# blinds_v60.net
KiCad netlist of a schematic drawn in EAGLE
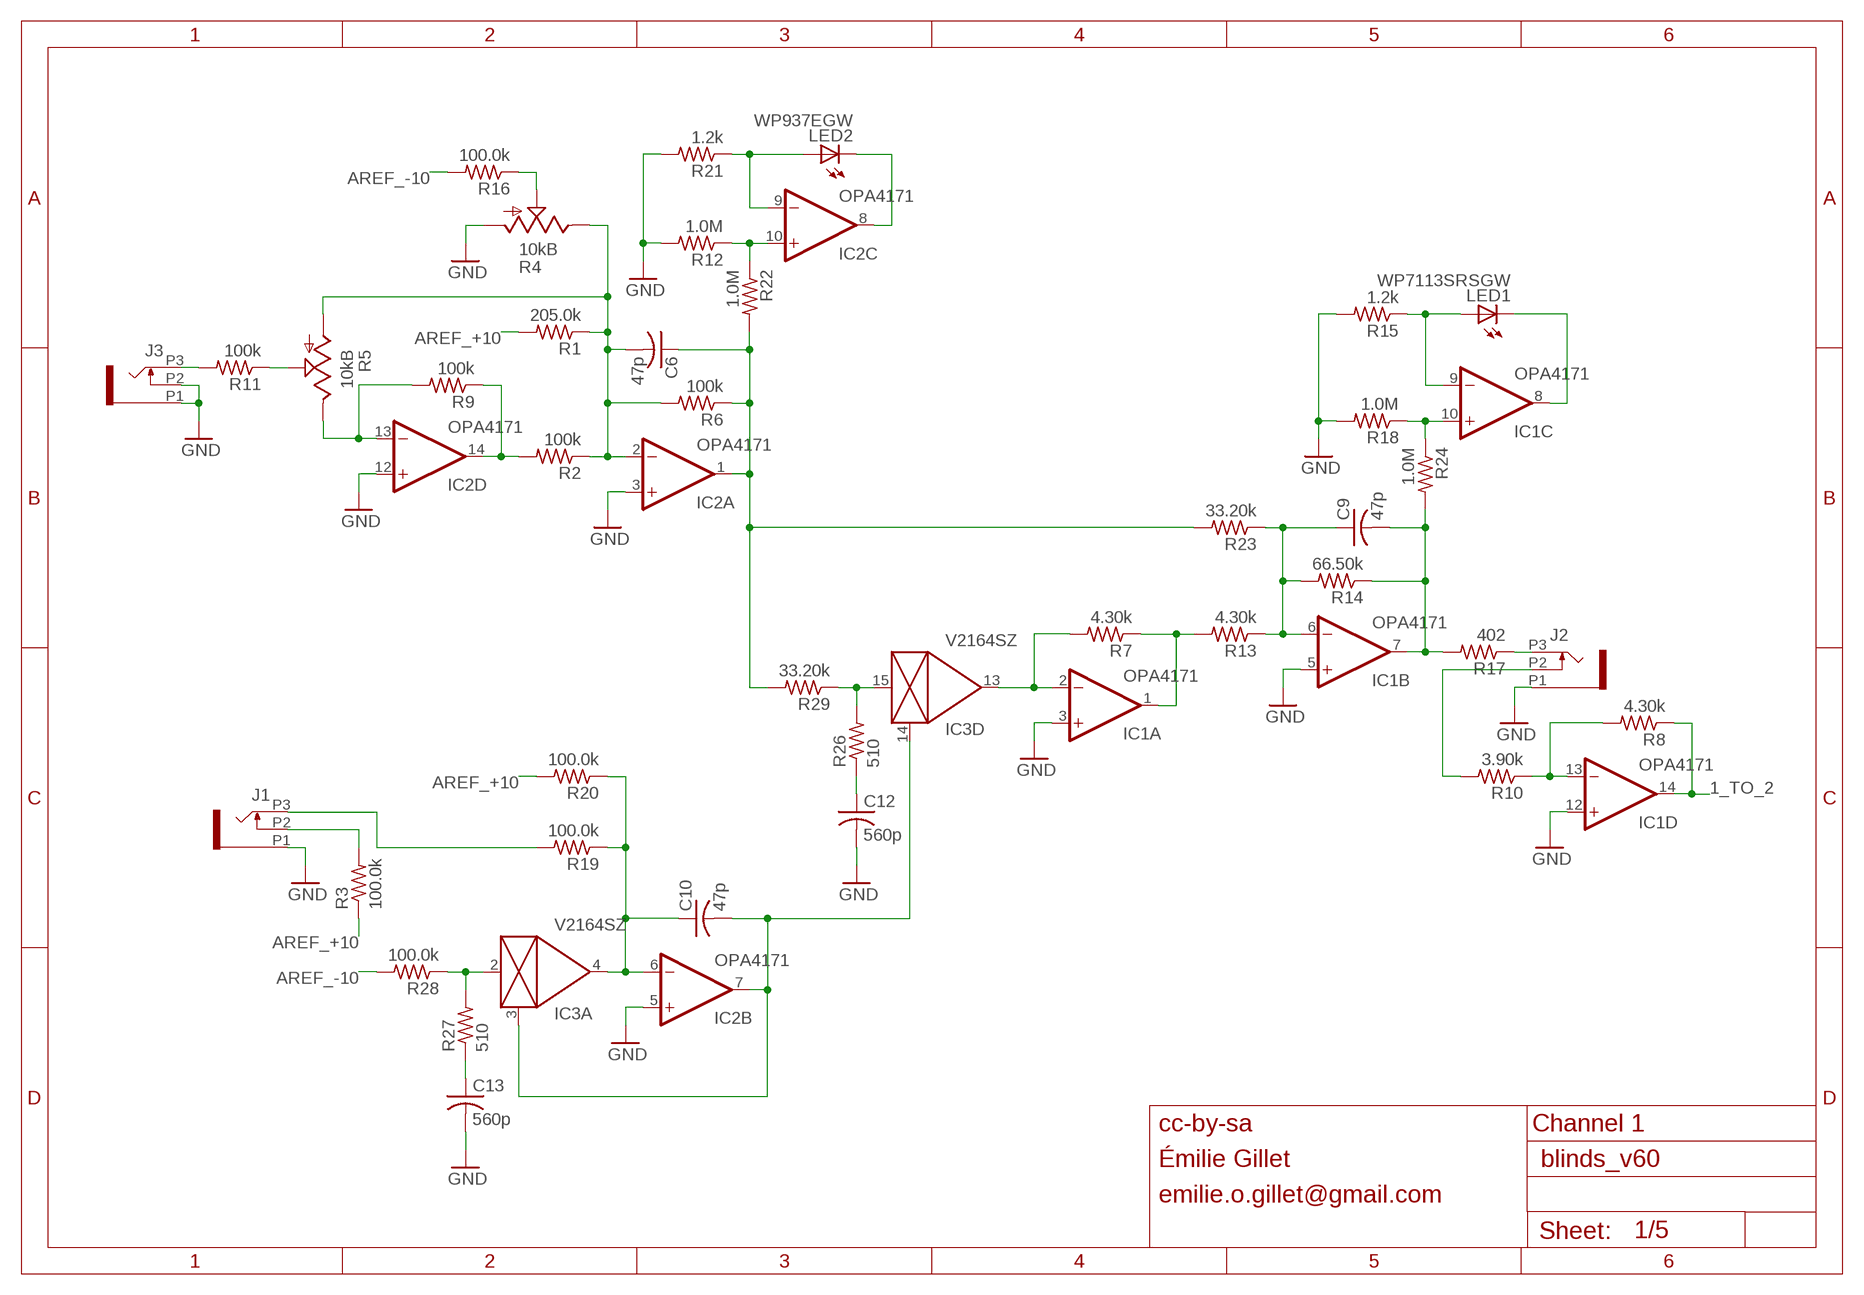
[diagram p0: schematic, sheet 1]
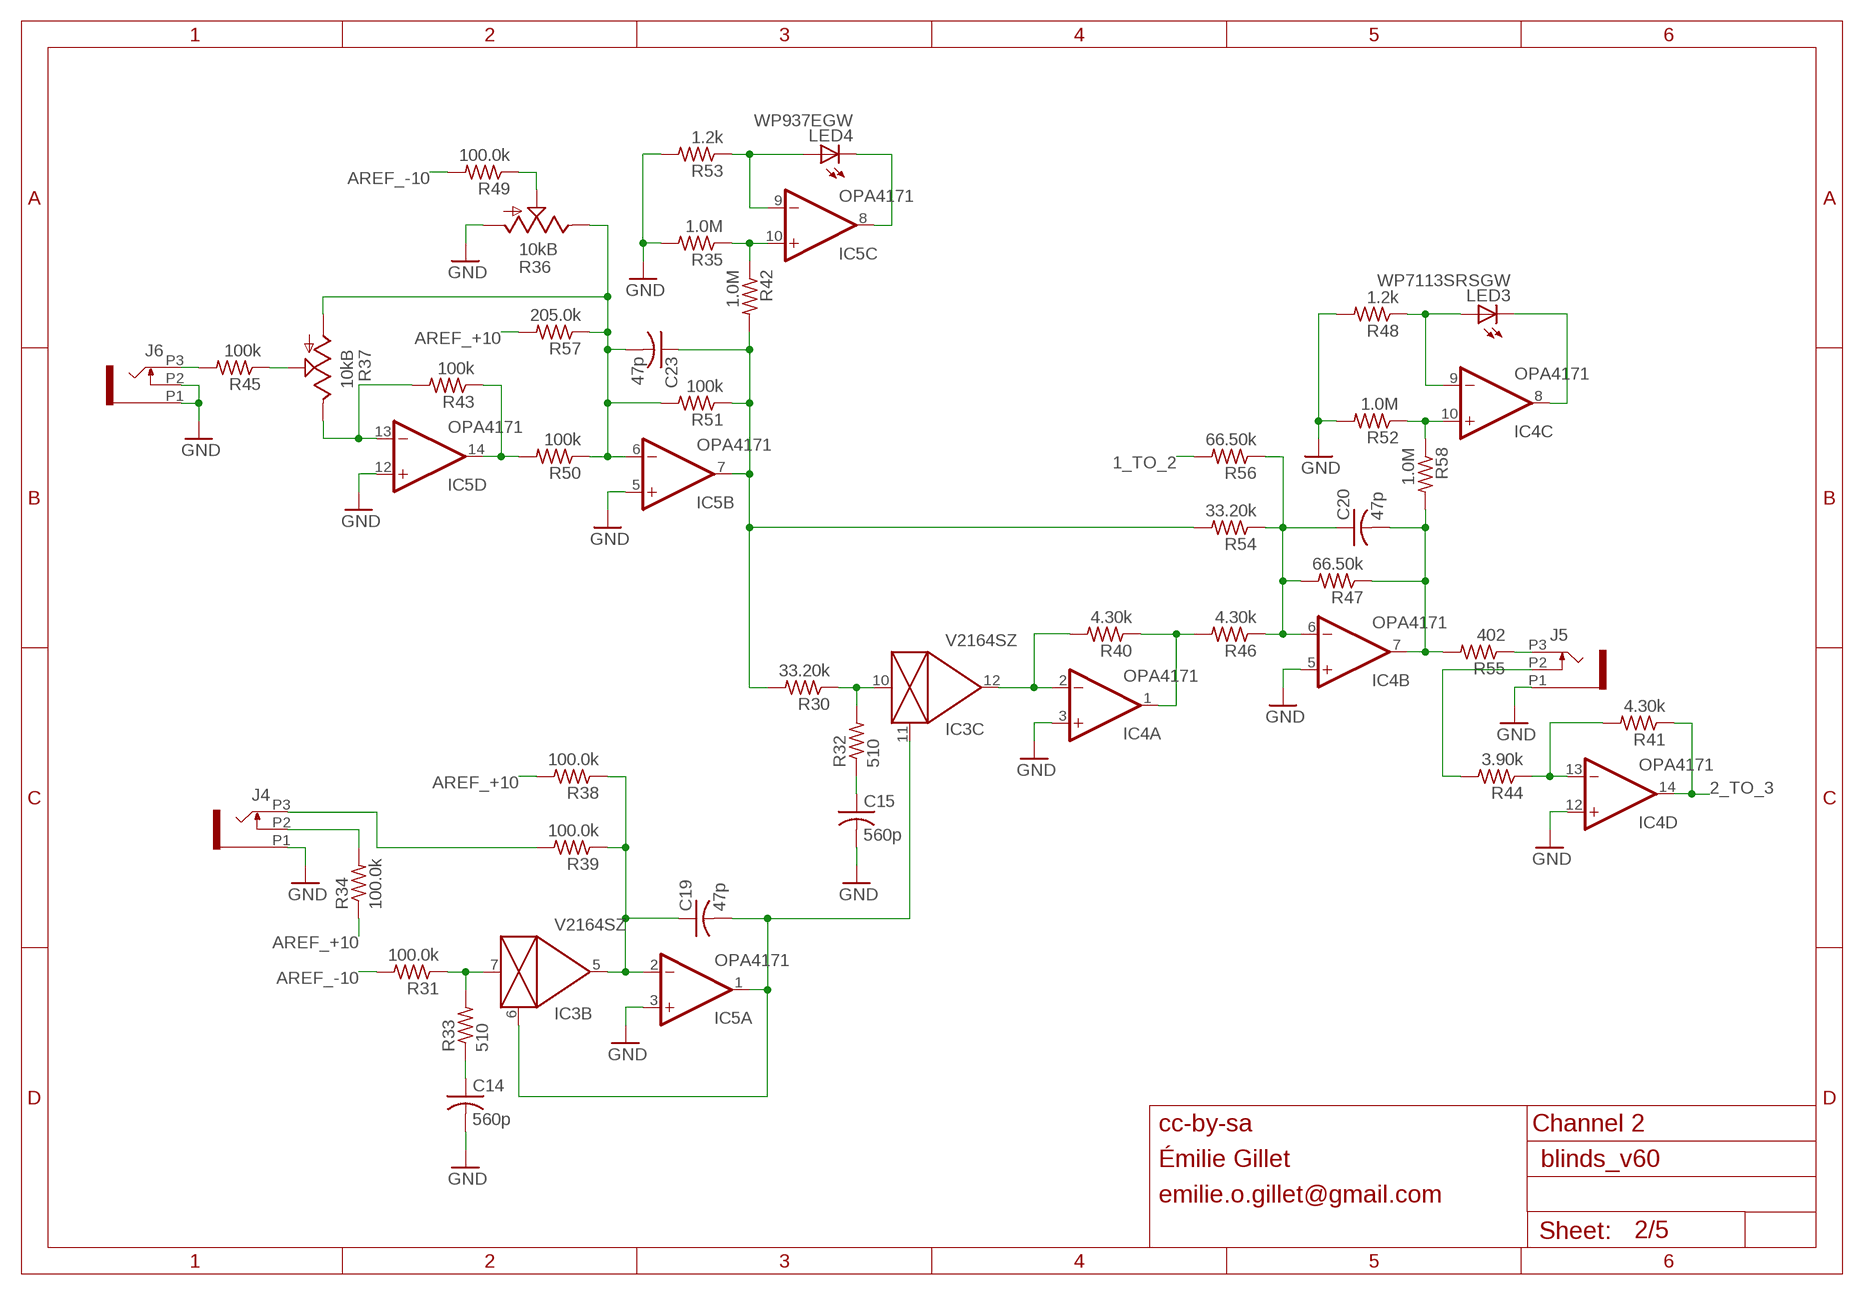
[diagram p1: schematic, sheet 2]
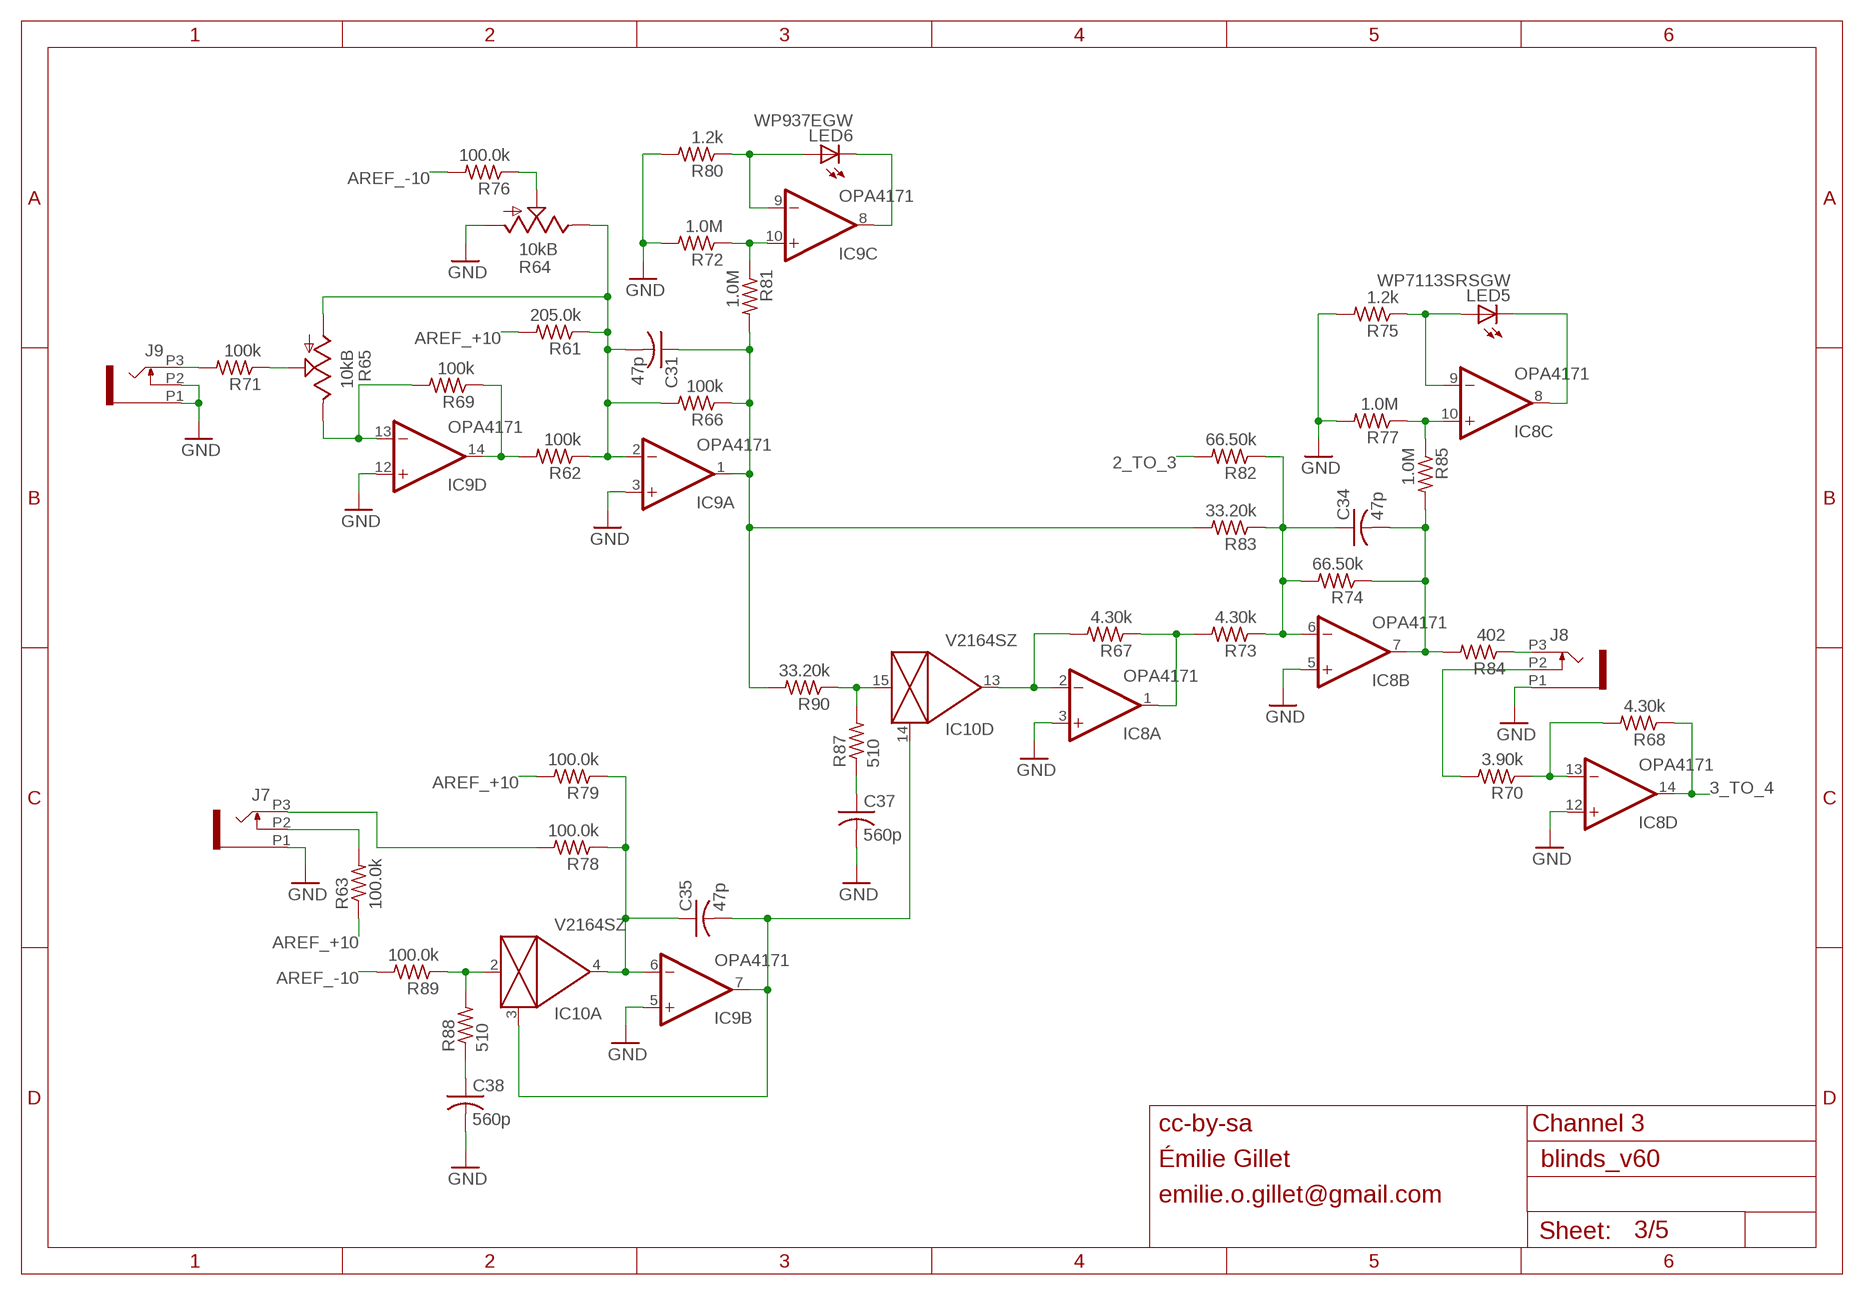
[diagram p2: schematic, sheet 3]
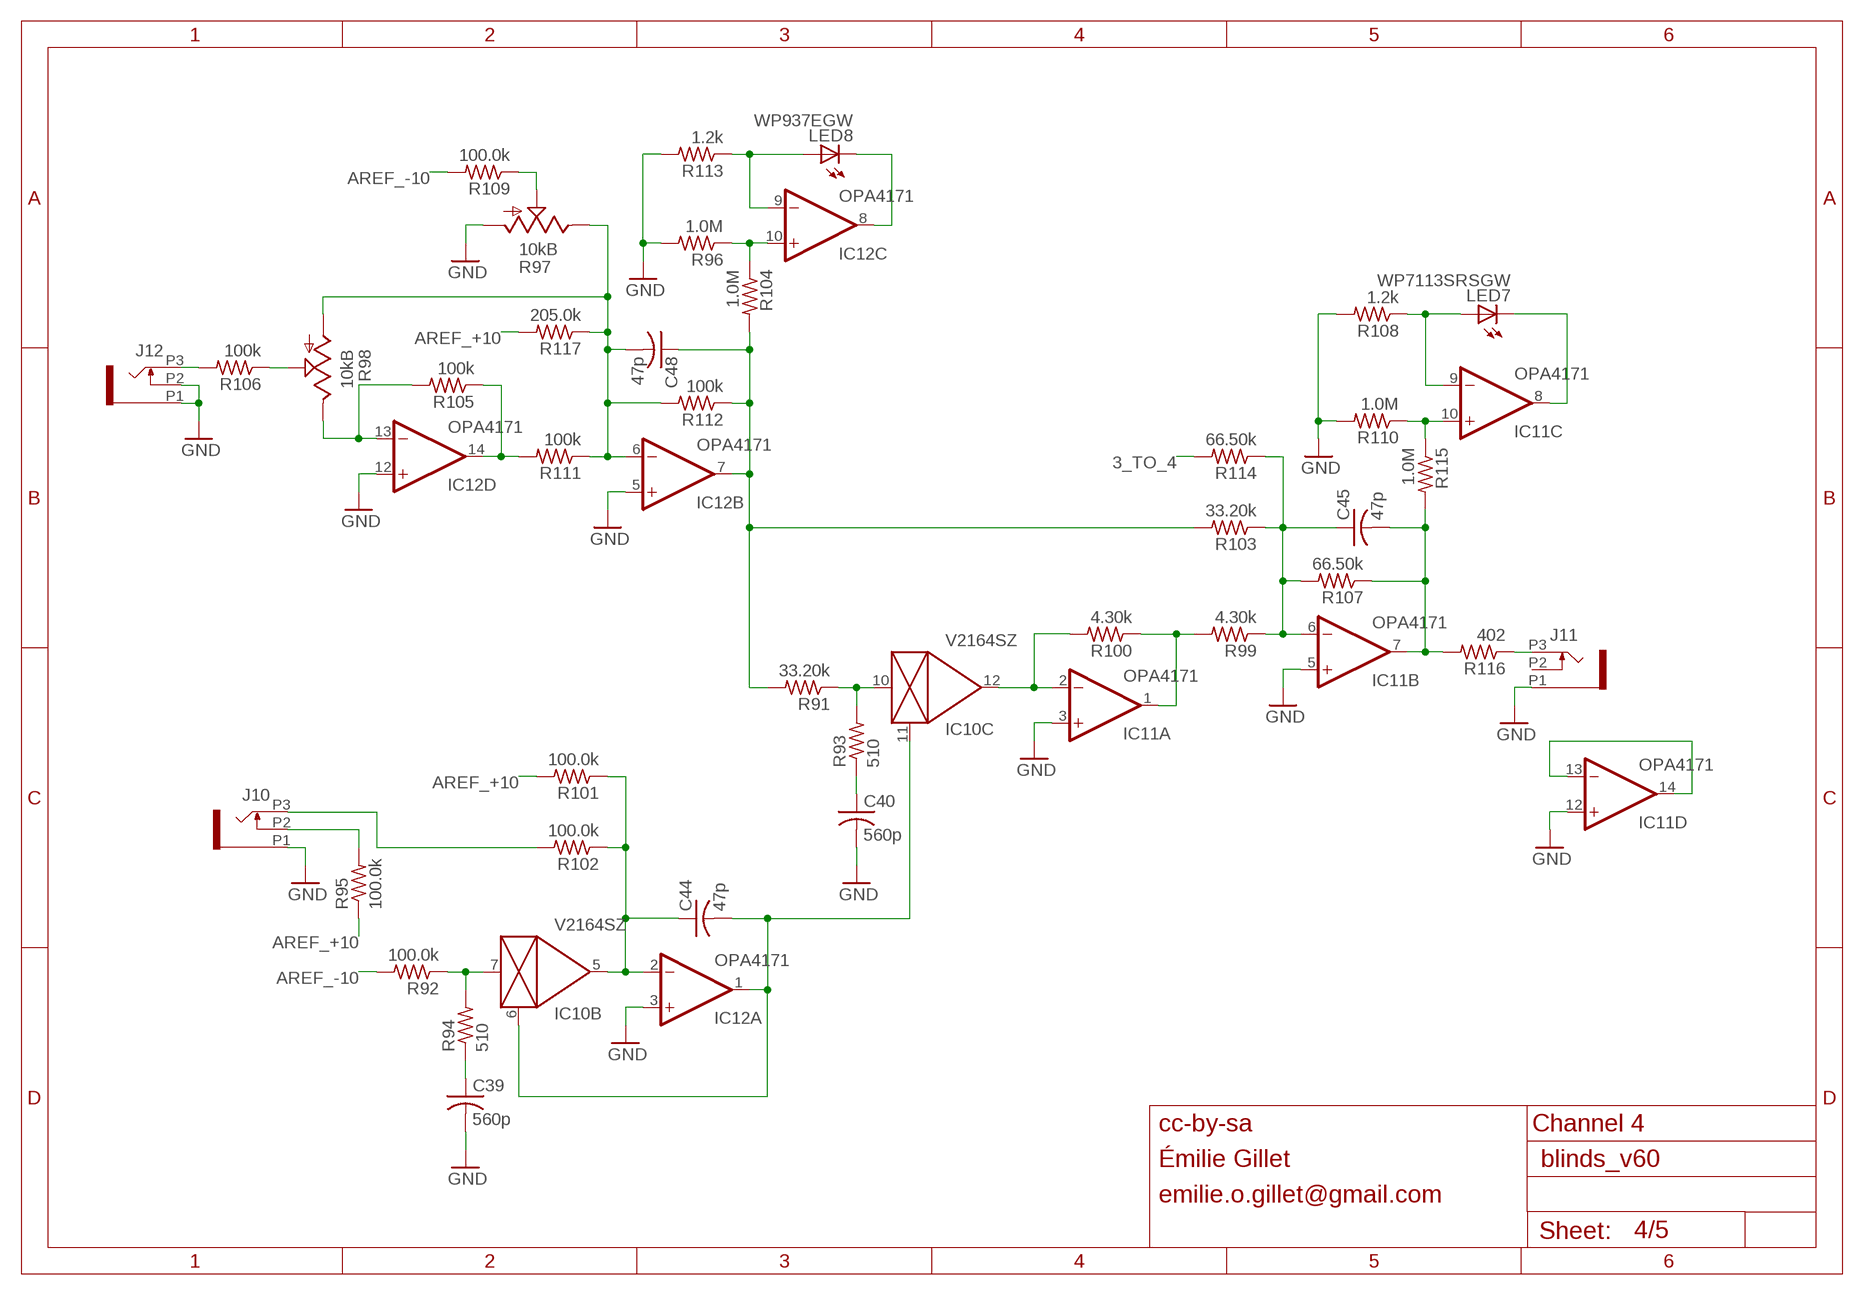
[diagram p3: schematic, sheet 4]
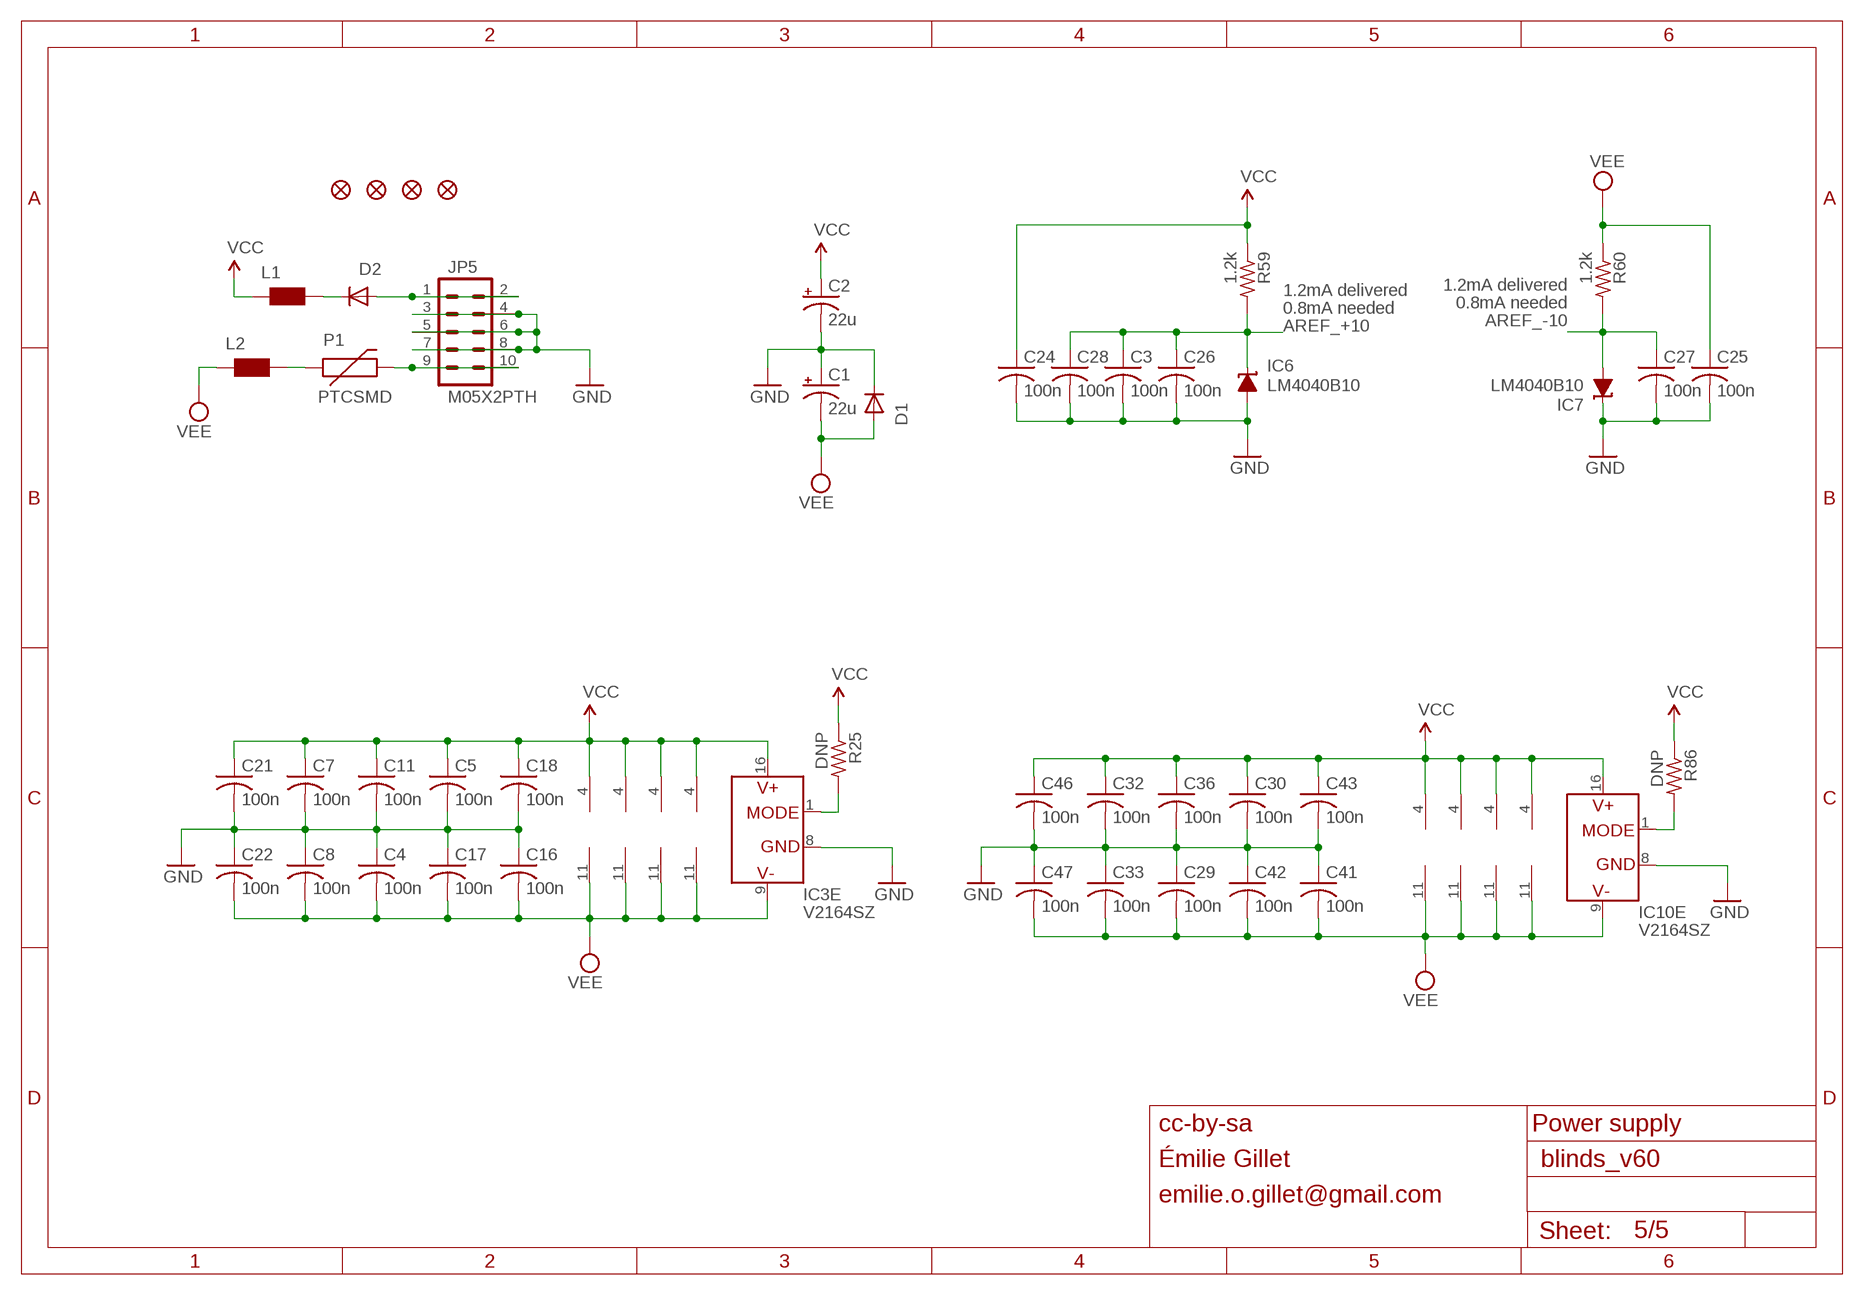
[diagram p4: schematic, sheet 5]

(export (version "E")
  (design (tool "Eeschema 10.0.6"))
  (components
    (comp (ref "C14")
      (value "560p")
      (footprint "eagle-import:C0603")
      (libsource (lib "eagle-import") (part "C-USC0603"))
    )
    (comp (ref "C15")
      (value "560p")
      (footprint "eagle-import:C0603")
      (libsource (lib "eagle-import") (part "C-USC0603"))
    )
    (comp (ref "C19")
      (value "47p")
      (footprint "eagle-import:C0603")
      (libsource (lib "eagle-import") (part "C-USC0603"))
    )
    (comp (ref "C20")
      (value "47p")
      (footprint "eagle-import:C0603")
      (libsource (lib "eagle-import") (part "C-USC0603"))
    )
    (comp (ref "C23")
      (value "47p")
      (footprint "eagle-import:C0603")
      (libsource (lib "eagle-import") (part "C-USC0603"))
    )
    (comp (ref "IC3")
      (value "V2164SZ")
      (footprint "eagle-import:SOIC16N")
      (libsource (lib "eagle-import") (part "SSM2164S"))
    )
    (comp (ref "IC4")
      (value "OPA4171")
      (footprint "eagle-import:TSSOP14")
      (libsource (lib "eagle-import") (part "TL074PW"))
    )
    (comp (ref "IC5")
      (value "OPA4171")
      (footprint "eagle-import:TSSOP14")
      (libsource (lib "eagle-import") (part "TL074PW"))
    )
    (comp (ref "J4")
      (value "PJ301_THONKICONN6")
      (footprint "eagle-import:WQP_PJ_301M6")
      (libsource (lib "eagle-import") (part "PJ301_THONKICONN6"))
    )
    (comp (ref "J5")
      (value "PJ301_THONKICONN6")
      (footprint "eagle-import:WQP_PJ_301M6")
      (libsource (lib "eagle-import") (part "PJ301_THONKICONN6"))
    )
    (comp (ref "J6")
      (value "PJ301_THONKICONN6")
      (footprint "eagle-import:WQP_PJ_301M6")
      (libsource (lib "eagle-import") (part "PJ301_THONKICONN6"))
    )
    (comp (ref "LED3")
      (value "WP7113SRSGW")
      (footprint "eagle-import:LED5MM")
      (libsource (lib "eagle-import") (part "LED5MM"))
    )
    (comp (ref "LED4")
      (value "WP937EGW")
      (footprint "eagle-import:LED3MM")
      (libsource (lib "eagle-import") (part "LED3MM"))
    )
    (comp (ref "R30")
      (value "33.20k")
      (footprint "eagle-import:R0603")
      (libsource (lib "eagle-import") (part "R-US_R0603"))
    )
    (comp (ref "R31")
      (value "100.0k")
      (footprint "eagle-import:R0603")
      (libsource (lib "eagle-import") (part "R-US_R0603"))
    )
    (comp (ref "R32")
      (value "510")
      (footprint "eagle-import:R0603")
      (libsource (lib "eagle-import") (part "R-US_R0603"))
    )
    (comp (ref "R33")
      (value "510")
      (footprint "eagle-import:R0603")
      (libsource (lib "eagle-import") (part "R-US_R0603"))
    )
    (comp (ref "R34")
      (value "100.0k")
      (footprint "eagle-import:R0603")
      (libsource (lib "eagle-import") (part "R-US_R0603"))
    )
    (comp (ref "R35")
      (value "1.0M")
      (footprint "eagle-import:R0603")
      (libsource (lib "eagle-import") (part "R-US_R0603"))
    )
    (comp (ref "R36")
      (value "10kB")
      (footprint "eagle-import:ALPS_POT_VERTICAL_PS")
      (libsource (lib "eagle-import") (part "POT_USVERTICAL_PS"))
    )
    (comp (ref "R37")
      (value "10kB")
      (footprint "eagle-import:ALPS_POT_VERTICAL")
      (libsource (lib "eagle-import") (part "POT_USVERTICAL"))
    )
    (comp (ref "R38")
      (value "100.0k")
      (footprint "eagle-import:R0603")
      (libsource (lib "eagle-import") (part "R-US_R0603"))
    )
    (comp (ref "R39")
      (value "100.0k")
      (footprint "eagle-import:R0603")
      (libsource (lib "eagle-import") (part "R-US_R0603"))
    )
    (comp (ref "R40")
      (value "4.30k")
      (footprint "eagle-import:R0603")
      (libsource (lib "eagle-import") (part "R-US_R0603"))
    )
    (comp (ref "R41")
      (value "4.30k")
      (footprint "eagle-import:R0603")
      (libsource (lib "eagle-import") (part "R-US_R0603"))
    )
    (comp (ref "R42")
      (value "1.0M")
      (footprint "eagle-import:R0603")
      (libsource (lib "eagle-import") (part "R-US_R0603"))
    )
    (comp (ref "R43")
      (value "100k")
      (footprint "eagle-import:R0603")
      (libsource (lib "eagle-import") (part "R-US_R0603"))
    )
    (comp (ref "R44")
      (value "3.90k")
      (footprint "eagle-import:R0603")
      (libsource (lib "eagle-import") (part "R-US_R0603"))
    )
    (comp (ref "R45")
      (value "100k")
      (footprint "eagle-import:R0603")
      (libsource (lib "eagle-import") (part "R-US_R0603"))
    )
    (comp (ref "R46")
      (value "4.30k")
      (footprint "eagle-import:R0603")
      (libsource (lib "eagle-import") (part "R-US_R0603"))
    )
    (comp (ref "R47")
      (value "66.50k")
      (footprint "eagle-import:R0603")
      (libsource (lib "eagle-import") (part "R-US_R0603"))
    )
    (comp (ref "R48")
      (value "1.2k")
      (footprint "eagle-import:R0603")
      (libsource (lib "eagle-import") (part "R-US_R0603"))
    )
    (comp (ref "R49")
      (value "100.0k")
      (footprint "eagle-import:R0603")
      (libsource (lib "eagle-import") (part "R-US_R0603"))
    )
    (comp (ref "R50")
      (value "100k")
      (footprint "eagle-import:R0603")
      (libsource (lib "eagle-import") (part "R-US_R0603"))
    )
    (comp (ref "R51")
      (value "100k")
      (footprint "eagle-import:R0603")
      (libsource (lib "eagle-import") (part "R-US_R0603"))
    )
    (comp (ref "R52")
      (value "1.0M")
      (footprint "eagle-import:R0603")
      (libsource (lib "eagle-import") (part "R-US_R0603"))
    )
    (comp (ref "R53")
      (value "1.2k")
      (footprint "eagle-import:R0603")
      (libsource (lib "eagle-import") (part "R-US_R0603"))
    )
    (comp (ref "R54")
      (value "33.20k")
      (footprint "eagle-import:R0603")
      (libsource (lib "eagle-import") (part "R-US_R0603"))
    )
    (comp (ref "R55")
      (value "402")
      (footprint "eagle-import:R0603")
      (libsource (lib "eagle-import") (part "R-US_R0603"))
    )
    (comp (ref "R56")
      (value "66.50k")
      (footprint "eagle-import:R0603")
      (libsource (lib "eagle-import") (part "R-US_R0603"))
    )
    (comp (ref "R57")
      (value "205.0k")
      (footprint "eagle-import:R0603")
      (libsource (lib "eagle-import") (part "R-US_R0603"))
    )
    (comp (ref "R58")
      (value "1.0M")
      (footprint "eagle-import:R0603")
      (libsource (lib "eagle-import") (part "R-US_R0603"))
    )
    (comp (ref "C39")
      (value "560p")
      (footprint "eagle-import:C0603")
      (libsource (lib "eagle-import") (part "C-USC0603"))
    )
    (comp (ref "C40")
      (value "560p")
      (footprint "eagle-import:C0603")
      (libsource (lib "eagle-import") (part "C-USC0603"))
    )
    (comp (ref "C44")
      (value "47p")
      (footprint "eagle-import:C0603")
      (libsource (lib "eagle-import") (part "C-USC0603"))
    )
    (comp (ref "C45")
      (value "47p")
      (footprint "eagle-import:C0603")
      (libsource (lib "eagle-import") (part "C-USC0603"))
    )
    (comp (ref "C48")
      (value "47p")
      (footprint "eagle-import:C0603")
      (libsource (lib "eagle-import") (part "C-USC0603"))
    )
    (comp (ref "IC10")
      (value "V2164SZ")
      (footprint "eagle-import:SOIC16N")
      (libsource (lib "eagle-import") (part "SSM2164S"))
    )
    (comp (ref "IC11")
      (value "OPA4171")
      (footprint "eagle-import:TSSOP14")
      (libsource (lib "eagle-import") (part "TL074PW"))
    )
    (comp (ref "IC12")
      (value "OPA4171")
      (footprint "eagle-import:TSSOP14")
      (libsource (lib "eagle-import") (part "TL074PW"))
    )
    (comp (ref "J10")
      (value "PJ301_THONKICONN6")
      (footprint "eagle-import:WQP_PJ_301M6")
      (libsource (lib "eagle-import") (part "PJ301_THONKICONN6"))
    )
    (comp (ref "J11")
      (value "PJ301_THONKICONN6")
      (footprint "eagle-import:WQP_PJ_301M6")
      (libsource (lib "eagle-import") (part "PJ301_THONKICONN6"))
    )
    (comp (ref "J12")
      (value "PJ301_THONKICONN6")
      (footprint "eagle-import:WQP_PJ_301M6")
      (libsource (lib "eagle-import") (part "PJ301_THONKICONN6"))
    )
    (comp (ref "LED7")
      (value "WP7113SRSGW")
      (footprint "eagle-import:LED5MM")
      (libsource (lib "eagle-import") (part "LED5MM"))
    )
    (comp (ref "LED8")
      (value "WP937EGW")
      (footprint "eagle-import:LED3MM")
      (libsource (lib "eagle-import") (part "LED3MM"))
    )
    (comp (ref "R91")
      (value "33.20k")
      (footprint "eagle-import:R0603")
      (libsource (lib "eagle-import") (part "R-US_R0603"))
    )
    (comp (ref "R92")
      (value "100.0k")
      (footprint "eagle-import:R0603")
      (libsource (lib "eagle-import") (part "R-US_R0603"))
    )
    (comp (ref "R93")
      (value "510")
      (footprint "eagle-import:R0603")
      (libsource (lib "eagle-import") (part "R-US_R0603"))
    )
    (comp (ref "R94")
      (value "510")
      (footprint "eagle-import:R0603")
      (libsource (lib "eagle-import") (part "R-US_R0603"))
    )
    (comp (ref "R95")
      (value "100.0k")
      (footprint "eagle-import:R0603")
      (libsource (lib "eagle-import") (part "R-US_R0603"))
    )
    (comp (ref "R96")
      (value "1.0M")
      (footprint "eagle-import:R0603")
      (libsource (lib "eagle-import") (part "R-US_R0603"))
    )
    (comp (ref "R97")
      (value "10kB")
      (footprint "eagle-import:ALPS_POT_VERTICAL_PS")
      (libsource (lib "eagle-import") (part "POT_USVERTICAL_PS"))
    )
    (comp (ref "R98")
      (value "10kB")
      (footprint "eagle-import:ALPS_POT_VERTICAL")
      (libsource (lib "eagle-import") (part "POT_USVERTICAL"))
    )
    (comp (ref "R99")
      (value "4.30k")
      (footprint "eagle-import:R0603")
      (libsource (lib "eagle-import") (part "R-US_R0603"))
    )
    (comp (ref "R100")
      (value "4.30k")
      (footprint "eagle-import:R0603")
      (libsource (lib "eagle-import") (part "R-US_R0603"))
    )
    (comp (ref "R101")
      (value "100.0k")
      (footprint "eagle-import:R0603")
      (libsource (lib "eagle-import") (part "R-US_R0603"))
    )
    (comp (ref "R102")
      (value "100.0k")
      (footprint "eagle-import:R0603")
      (libsource (lib "eagle-import") (part "R-US_R0603"))
    )
    (comp (ref "R103")
      (value "33.20k")
      (footprint "eagle-import:R0603")
      (libsource (lib "eagle-import") (part "R-US_R0603"))
    )
    (comp (ref "R104")
      (value "1.0M")
      (footprint "eagle-import:R0603")
      (libsource (lib "eagle-import") (part "R-US_R0603"))
    )
    (comp (ref "R105")
      (value "100k")
      (footprint "eagle-import:R0603")
      (libsource (lib "eagle-import") (part "R-US_R0603"))
    )
    (comp (ref "R106")
      (value "100k")
      (footprint "eagle-import:R0603")
      (libsource (lib "eagle-import") (part "R-US_R0603"))
    )
    (comp (ref "R107")
      (value "66.50k")
      (footprint "eagle-import:R0603")
      (libsource (lib "eagle-import") (part "R-US_R0603"))
    )
    (comp (ref "R108")
      (value "1.2k")
      (footprint "eagle-import:R0603")
      (libsource (lib "eagle-import") (part "R-US_R0603"))
    )
    (comp (ref "R109")
      (value "100.0k")
      (footprint "eagle-import:R0603")
      (libsource (lib "eagle-import") (part "R-US_R0603"))
    )
    (comp (ref "R110")
      (value "1.0M")
      (footprint "eagle-import:R0603")
      (libsource (lib "eagle-import") (part "R-US_R0603"))
    )
    (comp (ref "R111")
      (value "100k")
      (footprint "eagle-import:R0603")
      (libsource (lib "eagle-import") (part "R-US_R0603"))
    )
    (comp (ref "R112")
      (value "100k")
      (footprint "eagle-import:R0603")
      (libsource (lib "eagle-import") (part "R-US_R0603"))
    )
    (comp (ref "R113")
      (value "1.2k")
      (footprint "eagle-import:R0603")
      (libsource (lib "eagle-import") (part "R-US_R0603"))
    )
    (comp (ref "R114")
      (value "66.50k")
      (footprint "eagle-import:R0603")
      (libsource (lib "eagle-import") (part "R-US_R0603"))
    )
    (comp (ref "R115")
      (value "1.0M")
      (footprint "eagle-import:R0603")
      (libsource (lib "eagle-import") (part "R-US_R0603"))
    )
    (comp (ref "R116")
      (value "402")
      (footprint "eagle-import:R0603")
      (libsource (lib "eagle-import") (part "R-US_R0603"))
    )
    (comp (ref "R117")
      (value "205.0k")
      (footprint "eagle-import:R0603")
      (libsource (lib "eagle-import") (part "R-US_R0603"))
    )
    (comp (ref "C6")
      (value "47p")
      (footprint "eagle-import:C0603")
      (libsource (lib "eagle-import") (part "C-USC0603"))
    )
    (comp (ref "C9")
      (value "47p")
      (footprint "eagle-import:C0603")
      (libsource (lib "eagle-import") (part "C-USC0603"))
    )
    (comp (ref "C10")
      (value "47p")
      (footprint "eagle-import:C0603")
      (libsource (lib "eagle-import") (part "C-USC0603"))
    )
    (comp (ref "C12")
      (value "560p")
      (footprint "eagle-import:C0603")
      (libsource (lib "eagle-import") (part "C-USC0603"))
    )
    (comp (ref "C13")
      (value "560p")
      (footprint "eagle-import:C0603")
      (libsource (lib "eagle-import") (part "C-USC0603"))
    )
    (comp (ref "IC1")
      (value "OPA4171")
      (footprint "eagle-import:TSSOP14")
      (libsource (lib "eagle-import") (part "TL074PW"))
    )
    (comp (ref "IC2")
      (value "OPA4171")
      (footprint "eagle-import:TSSOP14")
      (libsource (lib "eagle-import") (part "TL074PW"))
    )
    (comp (ref "J1")
      (value "PJ301_THONKICONN6")
      (footprint "eagle-import:WQP_PJ_301M6")
      (libsource (lib "eagle-import") (part "PJ301_THONKICONN6"))
    )
    (comp (ref "J2")
      (value "PJ301_THONKICONN6")
      (footprint "eagle-import:WQP_PJ_301M6")
      (libsource (lib "eagle-import") (part "PJ301_THONKICONN6"))
    )
    (comp (ref "J3")
      (value "PJ301_THONKICONN6")
      (footprint "eagle-import:WQP_PJ_301M6")
      (libsource (lib "eagle-import") (part "PJ301_THONKICONN6"))
    )
    (comp (ref "LED1")
      (value "WP7113SRSGW")
      (footprint "eagle-import:LED5MM")
      (libsource (lib "eagle-import") (part "LED5MM"))
    )
    (comp (ref "LED2")
      (value "WP937EGW")
      (footprint "eagle-import:LED3MM")
      (libsource (lib "eagle-import") (part "LED3MM"))
    )
    (comp (ref "R1")
      (value "205.0k")
      (footprint "eagle-import:R0603")
      (libsource (lib "eagle-import") (part "R-US_R0603"))
    )
    (comp (ref "R2")
      (value "100k")
      (footprint "eagle-import:R0603")
      (libsource (lib "eagle-import") (part "R-US_R0603"))
    )
    (comp (ref "R3")
      (value "100.0k")
      (footprint "eagle-import:R0603")
      (libsource (lib "eagle-import") (part "R-US_R0603"))
    )
    (comp (ref "R4")
      (value "10kB")
      (footprint "eagle-import:ALPS_POT_VERTICAL_PS")
      (libsource (lib "eagle-import") (part "POT_USVERTICAL_PS"))
    )
    (comp (ref "R5")
      (value "10kB")
      (footprint "eagle-import:ALPS_POT_VERTICAL")
      (libsource (lib "eagle-import") (part "POT_USVERTICAL"))
    )
    (comp (ref "R6")
      (value "100k")
      (footprint "eagle-import:R0603")
      (libsource (lib "eagle-import") (part "R-US_R0603"))
    )
    (comp (ref "R7")
      (value "4.30k")
      (footprint "eagle-import:R0603")
      (libsource (lib "eagle-import") (part "R-US_R0603"))
    )
    (comp (ref "R8")
      (value "4.30k")
      (footprint "eagle-import:R0603")
      (libsource (lib "eagle-import") (part "R-US_R0603"))
    )
    (comp (ref "R9")
      (value "100k")
      (footprint "eagle-import:R0603")
      (libsource (lib "eagle-import") (part "R-US_R0603"))
    )
    (comp (ref "R10")
      (value "3.90k")
      (footprint "eagle-import:R0603")
      (libsource (lib "eagle-import") (part "R-US_R0603"))
    )
    (comp (ref "R11")
      (value "100k")
      (footprint "eagle-import:R0603")
      (libsource (lib "eagle-import") (part "R-US_R0603"))
    )
    (comp (ref "R12")
      (value "1.0M")
      (footprint "eagle-import:R0603")
      (libsource (lib "eagle-import") (part "R-US_R0603"))
    )
    (comp (ref "R13")
      (value "4.30k")
      (footprint "eagle-import:R0603")
      (libsource (lib "eagle-import") (part "R-US_R0603"))
    )
    (comp (ref "R14")
      (value "66.50k")
      (footprint "eagle-import:R0603")
      (libsource (lib "eagle-import") (part "R-US_R0603"))
    )
    (comp (ref "R15")
      (value "1.2k")
      (footprint "eagle-import:R0603")
      (libsource (lib "eagle-import") (part "R-US_R0603"))
    )
    (comp (ref "R16")
      (value "100.0k")
      (footprint "eagle-import:R0603")
      (libsource (lib "eagle-import") (part "R-US_R0603"))
    )
    (comp (ref "R17")
      (value "402")
      (footprint "eagle-import:R0603")
      (libsource (lib "eagle-import") (part "R-US_R0603"))
    )
    (comp (ref "R18")
      (value "1.0M")
      (footprint "eagle-import:R0603")
      (libsource (lib "eagle-import") (part "R-US_R0603"))
    )
    (comp (ref "R19")
      (value "100.0k")
      (footprint "eagle-import:R0603")
      (libsource (lib "eagle-import") (part "R-US_R0603"))
    )
    (comp (ref "R20")
      (value "100.0k")
      (footprint "eagle-import:R0603")
      (libsource (lib "eagle-import") (part "R-US_R0603"))
    )
    (comp (ref "R21")
      (value "1.2k")
      (footprint "eagle-import:R0603")
      (libsource (lib "eagle-import") (part "R-US_R0603"))
    )
    (comp (ref "R22")
      (value "1.0M")
      (footprint "eagle-import:R0603")
      (libsource (lib "eagle-import") (part "R-US_R0603"))
    )
    (comp (ref "R23")
      (value "33.20k")
      (footprint "eagle-import:R0603")
      (libsource (lib "eagle-import") (part "R-US_R0603"))
    )
    (comp (ref "R24")
      (value "1.0M")
      (footprint "eagle-import:R0603")
      (libsource (lib "eagle-import") (part "R-US_R0603"))
    )
    (comp (ref "R26")
      (value "510")
      (footprint "eagle-import:R0603")
      (libsource (lib "eagle-import") (part "R-US_R0603"))
    )
    (comp (ref "R27")
      (value "510")
      (footprint "eagle-import:R0603")
      (libsource (lib "eagle-import") (part "R-US_R0603"))
    )
    (comp (ref "R28")
      (value "100.0k")
      (footprint "eagle-import:R0603")
      (libsource (lib "eagle-import") (part "R-US_R0603"))
    )
    (comp (ref "R29")
      (value "33.20k")
      (footprint "eagle-import:R0603")
      (libsource (lib "eagle-import") (part "R-US_R0603"))
    )
    (comp (ref "C1")
      (value "22u")
      (footprint "eagle-import:PANASONIC_C")
      (libsource (lib "eagle-import") (part "CPOL-USC"))
    )
    (comp (ref "C2")
      (value "22u")
      (footprint "eagle-import:PANASONIC_C")
      (libsource (lib "eagle-import") (part "CPOL-USC"))
    )
    (comp (ref "C3")
      (value "100n")
      (footprint "eagle-import:C0603")
      (libsource (lib "eagle-import") (part "C-USC0603"))
    )
    (comp (ref "C4")
      (value "100n")
      (footprint "eagle-import:C0603")
      (libsource (lib "eagle-import") (part "C-USC0603"))
    )
    (comp (ref "C5")
      (value "100n")
      (footprint "eagle-import:C0603")
      (libsource (lib "eagle-import") (part "C-USC0603"))
    )
    (comp (ref "C7")
      (value "100n")
      (footprint "eagle-import:C0603")
      (libsource (lib "eagle-import") (part "C-USC0603"))
    )
    (comp (ref "C8")
      (value "100n")
      (footprint "eagle-import:C0603")
      (libsource (lib "eagle-import") (part "C-USC0603"))
    )
    (comp (ref "C11")
      (value "100n")
      (footprint "eagle-import:C0603")
      (libsource (lib "eagle-import") (part "C-USC0603"))
    )
    (comp (ref "C16")
      (value "100n")
      (footprint "eagle-import:C0603")
      (libsource (lib "eagle-import") (part "C-USC0603"))
    )
    (comp (ref "C17")
      (value "100n")
      (footprint "eagle-import:C0603")
      (libsource (lib "eagle-import") (part "C-USC0603"))
    )
    (comp (ref "C18")
      (value "100n")
      (footprint "eagle-import:C0603")
      (libsource (lib "eagle-import") (part "C-USC0603"))
    )
    (comp (ref "C21")
      (value "100n")
      (footprint "eagle-import:C0603")
      (libsource (lib "eagle-import") (part "C-USC0603"))
    )
    (comp (ref "C22")
      (value "100n")
      (footprint "eagle-import:C0603")
      (libsource (lib "eagle-import") (part "C-USC0603"))
    )
    (comp (ref "C24")
      (value "100n")
      (footprint "eagle-import:C0603")
      (libsource (lib "eagle-import") (part "C-USC0603"))
    )
    (comp (ref "C25")
      (value "100n")
      (footprint "eagle-import:C0603")
      (libsource (lib "eagle-import") (part "C-USC0603"))
    )
    (comp (ref "C26")
      (value "100n")
      (footprint "eagle-import:C0603")
      (libsource (lib "eagle-import") (part "C-USC0603"))
    )
    (comp (ref "C27")
      (value "100n")
      (footprint "eagle-import:C0603")
      (libsource (lib "eagle-import") (part "C-USC0603"))
    )
    (comp (ref "C28")
      (value "100n")
      (footprint "eagle-import:C0603")
      (libsource (lib "eagle-import") (part "C-USC0603"))
    )
    (comp (ref "C29")
      (value "100n")
      (footprint "eagle-import:C0603")
      (libsource (lib "eagle-import") (part "C-USC0603"))
    )
    (comp (ref "C30")
      (value "100n")
      (footprint "eagle-import:C0603")
      (libsource (lib "eagle-import") (part "C-USC0603"))
    )
    (comp (ref "C32")
      (value "100n")
      (footprint "eagle-import:C0603")
      (libsource (lib "eagle-import") (part "C-USC0603"))
    )
    (comp (ref "C33")
      (value "100n")
      (footprint "eagle-import:C0603")
      (libsource (lib "eagle-import") (part "C-USC0603"))
    )
    (comp (ref "C36")
      (value "100n")
      (footprint "eagle-import:C0603")
      (libsource (lib "eagle-import") (part "C-USC0603"))
    )
    (comp (ref "C41")
      (value "100n")
      (footprint "eagle-import:C0603")
      (libsource (lib "eagle-import") (part "C-USC0603"))
    )
    (comp (ref "C42")
      (value "100n")
      (footprint "eagle-import:C0603")
      (libsource (lib "eagle-import") (part "C-USC0603"))
    )
    (comp (ref "C43")
      (value "100n")
      (footprint "eagle-import:C0603")
      (libsource (lib "eagle-import") (part "C-USC0603"))
    )
    (comp (ref "C46")
      (value "100n")
      (footprint "eagle-import:C0603")
      (libsource (lib "eagle-import") (part "C-USC0603"))
    )
    (comp (ref "C47")
      (value "100n")
      (footprint "eagle-import:C0603")
      (libsource (lib "eagle-import") (part "C-USC0603"))
    )
    (comp (ref "D1")
      (value "1N5819HW")
      (footprint "eagle-import:SOD123")
      (libsource (lib "eagle-import") (part "DIODE-SOD123"))
    )
    (comp (ref "D2")
      (value "1N5819HW")
      (footprint "eagle-import:SOD123")
      (libsource (lib "eagle-import") (part "DIODE-SOD123"))
    )
    (comp (ref "IC6")
      (value "LM4040B10")
      (footprint "eagle-import:DBZ_R-PDSO-G3")
      (libsource (lib "eagle-import") (part "LM4041DBZB12"))
    )
    (comp (ref "IC7")
      (value "LM4040B10")
      (footprint "eagle-import:DBZ_R-PDSO-G3")
      (libsource (lib "eagle-import") (part "LM4041DBZB12"))
    )
    (comp (ref "IC8")
      (value "OPA4171")
      (footprint "eagle-import:TSSOP14")
      (libsource (lib "eagle-import") (part "TL074PW"))
    )
    (comp (ref "IC9")
      (value "OPA4171")
      (footprint "eagle-import:TSSOP14")
      (libsource (lib "eagle-import") (part "TL074PW"))
    )
    (comp (ref "JP1")
      (value "FIDUCIAL1X2")
      (footprint "eagle-import:FIDUCIAL-1X2")
      (libsource (lib "eagle-import") (part "FIDUCIAL1X2"))
    )
    (comp (ref "JP2")
      (value "FIDUCIAL1X2")
      (footprint "eagle-import:FIDUCIAL-1X2")
      (libsource (lib "eagle-import") (part "FIDUCIAL1X2"))
    )
    (comp (ref "JP3")
      (value "FIDUCIAL1X2")
      (footprint "eagle-import:FIDUCIAL-1X2")
      (libsource (lib "eagle-import") (part "FIDUCIAL1X2"))
    )
    (comp (ref "JP4")
      (value "FIDUCIAL1X2")
      (footprint "eagle-import:FIDUCIAL-1X2")
      (libsource (lib "eagle-import") (part "FIDUCIAL1X2"))
    )
    (comp (ref "JP5")
      (value "M05X2PTH")
      (footprint "eagle-import:AVR_ICSP")
      (libsource (lib "eagle-import") (part "M05X2PTH"))
    )
    (comp (ref "L1")
      (value "WE-CBF_0603")
      (footprint "eagle-import:0603")
      (libsource (lib "eagle-import") (part "WE-CBF_0603"))
    )
    (comp (ref "L2")
      (value "WE-CBF_0603")
      (footprint "eagle-import:0603")
      (libsource (lib "eagle-import") (part "WE-CBF_0603"))
    )
    (comp (ref "P1")
      (value "PTCSMD")
      (footprint "eagle-import:PTC-1206")
      (libsource (lib "eagle-import") (part "PTCSMD"))
    )
    (comp (ref "R25")
      (value "DNP")
      (footprint "eagle-import:R0603")
      (libsource (lib "eagle-import") (part "R-US_R0603"))
    )
    (comp (ref "R59")
      (value "1.2k")
      (footprint "eagle-import:R0603")
      (libsource (lib "eagle-import") (part "R-US_R0603"))
    )
    (comp (ref "R60")
      (value "1.2k")
      (footprint "eagle-import:R0603")
      (libsource (lib "eagle-import") (part "R-US_R0603"))
    )
    (comp (ref "R86")
      (value "DNP")
      (footprint "eagle-import:R0603")
      (libsource (lib "eagle-import") (part "R-US_R0603"))
    )
    (comp (ref "C31")
      (value "47p")
      (footprint "eagle-import:C0603")
      (libsource (lib "eagle-import") (part "C-USC0603"))
    )
    (comp (ref "C34")
      (value "47p")
      (footprint "eagle-import:C0603")
      (libsource (lib "eagle-import") (part "C-USC0603"))
    )
    (comp (ref "C35")
      (value "47p")
      (footprint "eagle-import:C0603")
      (libsource (lib "eagle-import") (part "C-USC0603"))
    )
    (comp (ref "C37")
      (value "560p")
      (footprint "eagle-import:C0603")
      (libsource (lib "eagle-import") (part "C-USC0603"))
    )
    (comp (ref "C38")
      (value "560p")
      (footprint "eagle-import:C0603")
      (libsource (lib "eagle-import") (part "C-USC0603"))
    )
    (comp (ref "J7")
      (value "PJ301_THONKICONN6")
      (footprint "eagle-import:WQP_PJ_301M6")
      (libsource (lib "eagle-import") (part "PJ301_THONKICONN6"))
    )
    (comp (ref "J8")
      (value "PJ301_THONKICONN6")
      (footprint "eagle-import:WQP_PJ_301M6")
      (libsource (lib "eagle-import") (part "PJ301_THONKICONN6"))
    )
    (comp (ref "J9")
      (value "PJ301_THONKICONN6")
      (footprint "eagle-import:WQP_PJ_301M6")
      (libsource (lib "eagle-import") (part "PJ301_THONKICONN6"))
    )
    (comp (ref "LED5")
      (value "WP7113SRSGW")
      (footprint "eagle-import:LED5MM")
      (libsource (lib "eagle-import") (part "LED5MM"))
    )
    (comp (ref "LED6")
      (value "WP937EGW")
      (footprint "eagle-import:LED3MM")
      (libsource (lib "eagle-import") (part "LED3MM"))
    )
    (comp (ref "R61")
      (value "205.0k")
      (footprint "eagle-import:R0603")
      (libsource (lib "eagle-import") (part "R-US_R0603"))
    )
    (comp (ref "R62")
      (value "100k")
      (footprint "eagle-import:R0603")
      (libsource (lib "eagle-import") (part "R-US_R0603"))
    )
    (comp (ref "R63")
      (value "100.0k")
      (footprint "eagle-import:R0603")
      (libsource (lib "eagle-import") (part "R-US_R0603"))
    )
    (comp (ref "R64")
      (value "10kB")
      (footprint "eagle-import:ALPS_POT_VERTICAL_PS")
      (libsource (lib "eagle-import") (part "POT_USVERTICAL_PS"))
    )
    (comp (ref "R65")
      (value "10kB")
      (footprint "eagle-import:ALPS_POT_VERTICAL")
      (libsource (lib "eagle-import") (part "POT_USVERTICAL"))
    )
    (comp (ref "R66")
      (value "100k")
      (footprint "eagle-import:R0603")
      (libsource (lib "eagle-import") (part "R-US_R0603"))
    )
    (comp (ref "R67")
      (value "4.30k")
      (footprint "eagle-import:R0603")
      (libsource (lib "eagle-import") (part "R-US_R0603"))
    )
    (comp (ref "R68")
      (value "4.30k")
      (footprint "eagle-import:R0603")
      (libsource (lib "eagle-import") (part "R-US_R0603"))
    )
    (comp (ref "R69")
      (value "100k")
      (footprint "eagle-import:R0603")
      (libsource (lib "eagle-import") (part "R-US_R0603"))
    )
    (comp (ref "R70")
      (value "3.90k")
      (footprint "eagle-import:R0603")
      (libsource (lib "eagle-import") (part "R-US_R0603"))
    )
    (comp (ref "R71")
      (value "100k")
      (footprint "eagle-import:R0603")
      (libsource (lib "eagle-import") (part "R-US_R0603"))
    )
    (comp (ref "R72")
      (value "1.0M")
      (footprint "eagle-import:R0603")
      (libsource (lib "eagle-import") (part "R-US_R0603"))
    )
    (comp (ref "R73")
      (value "4.30k")
      (footprint "eagle-import:R0603")
      (libsource (lib "eagle-import") (part "R-US_R0603"))
    )
    (comp (ref "R74")
      (value "66.50k")
      (footprint "eagle-import:R0603")
      (libsource (lib "eagle-import") (part "R-US_R0603"))
    )
    (comp (ref "R75")
      (value "1.2k")
      (footprint "eagle-import:R0603")
      (libsource (lib "eagle-import") (part "R-US_R0603"))
    )
    (comp (ref "R76")
      (value "100.0k")
      (footprint "eagle-import:R0603")
      (libsource (lib "eagle-import") (part "R-US_R0603"))
    )
    (comp (ref "R77")
      (value "1.0M")
      (footprint "eagle-import:R0603")
      (libsource (lib "eagle-import") (part "R-US_R0603"))
    )
    (comp (ref "R78")
      (value "100.0k")
      (footprint "eagle-import:R0603")
      (libsource (lib "eagle-import") (part "R-US_R0603"))
    )
    (comp (ref "R79")
      (value "100.0k")
      (footprint "eagle-import:R0603")
      (libsource (lib "eagle-import") (part "R-US_R0603"))
    )
    (comp (ref "R80")
      (value "1.2k")
      (footprint "eagle-import:R0603")
      (libsource (lib "eagle-import") (part "R-US_R0603"))
    )
    (comp (ref "R81")
      (value "1.0M")
      (footprint "eagle-import:R0603")
      (libsource (lib "eagle-import") (part "R-US_R0603"))
    )
    (comp (ref "R82")
      (value "66.50k")
      (footprint "eagle-import:R0603")
      (libsource (lib "eagle-import") (part "R-US_R0603"))
    )
    (comp (ref "R83")
      (value "33.20k")
      (footprint "eagle-import:R0603")
      (libsource (lib "eagle-import") (part "R-US_R0603"))
    )
    (comp (ref "R84")
      (value "402")
      (footprint "eagle-import:R0603")
      (libsource (lib "eagle-import") (part "R-US_R0603"))
    )
    (comp (ref "R85")
      (value "1.0M")
      (footprint "eagle-import:R0603")
      (libsource (lib "eagle-import") (part "R-US_R0603"))
    )
    (comp (ref "R87")
      (value "510")
      (footprint "eagle-import:R0603")
      (libsource (lib "eagle-import") (part "R-US_R0603"))
    )
    (comp (ref "R88")
      (value "510")
      (footprint "eagle-import:R0603")
      (libsource (lib "eagle-import") (part "R-US_R0603"))
    )
    (comp (ref "R89")
      (value "100.0k")
      (footprint "eagle-import:R0603")
      (libsource (lib "eagle-import") (part "R-US_R0603"))
    )
    (comp (ref "R90")
      (value "33.20k")
      (footprint "eagle-import:R0603")
      (libsource (lib "eagle-import") (part "R-US_R0603"))
    )
  )
  (nets
    (net (code "1") (name "1_TO_2") (class "Default")
      (node (ref "IC1") (pin "14") (pinfunction "OUT_14") (pintype "output"))
      (node (ref "R56") (pin "2") (pinfunction "2_2") (pintype "passive"))
      (node (ref "R8") (pin "1") (pinfunction "1_1") (pintype "passive"))
    )
    (net (code "2") (name "2_TO_3") (class "Default")
      (node (ref "IC4") (pin "14") (pinfunction "OUT_14") (pintype "output"))
      (node (ref "R41") (pin "1") (pinfunction "1_1") (pintype "passive"))
      (node (ref "R82") (pin "2") (pinfunction "2_2") (pintype "passive"))
    )
    (net (code "3") (name "3_TO_4") (class "Default")
      (node (ref "IC8") (pin "14") (pinfunction "OUT_14") (pintype "output"))
      (node (ref "R114") (pin "2") (pinfunction "2_2") (pintype "passive"))
      (node (ref "R68") (pin "1") (pinfunction "1_1") (pintype "passive"))
    )
    (net (code "4") (name "AREF_+10") (class "Default")
      (node (ref "C26") (pin "1") (pinfunction "1_1") (pintype "passive"))
      (node (ref "C28") (pin "1") (pinfunction "1_1") (pintype "passive"))
      (node (ref "C3") (pin "1") (pinfunction "1_1") (pintype "passive"))
      (node (ref "IC6") (pin "1") (pinfunction "C_1") (pintype "passive"))
      (node (ref "R1") (pin "2") (pinfunction "2_2") (pintype "passive"))
      (node (ref "R101") (pin "2") (pinfunction "2_2") (pintype "passive"))
      (node (ref "R117") (pin "2") (pinfunction "2_2") (pintype "passive"))
      (node (ref "R20") (pin "2") (pinfunction "2_2") (pintype "passive"))
      (node (ref "R3") (pin "1") (pinfunction "1_1") (pintype "passive"))
      (node (ref "R34") (pin "1") (pinfunction "1_1") (pintype "passive"))
      (node (ref "R38") (pin "2") (pinfunction "2_2") (pintype "passive"))
      (node (ref "R57") (pin "2") (pinfunction "2_2") (pintype "passive"))
      (node (ref "R59") (pin "2") (pinfunction "2_2") (pintype "passive"))
      (node (ref "R61") (pin "2") (pinfunction "2_2") (pintype "passive"))
      (node (ref "R63") (pin "1") (pinfunction "1_1") (pintype "passive"))
      (node (ref "R79") (pin "2") (pinfunction "2_2") (pintype "passive"))
      (node (ref "R95") (pin "1") (pinfunction "1_1") (pintype "passive"))
    )
    (net (code "5") (name "AREF_-10") (class "Default")
      (node (ref "C27") (pin "1") (pinfunction "1_1") (pintype "passive"))
      (node (ref "IC7") (pin "2") (pinfunction "A_2") (pintype "passive"))
      (node (ref "R109") (pin "2") (pinfunction "2_2") (pintype "passive"))
      (node (ref "R16") (pin "2") (pinfunction "2_2") (pintype "passive"))
      (node (ref "R28") (pin "2") (pinfunction "2_2") (pintype "passive"))
      (node (ref "R31") (pin "2") (pinfunction "2_2") (pintype "passive"))
      (node (ref "R49") (pin "2") (pinfunction "2_2") (pintype "passive"))
      (node (ref "R60") (pin "2") (pinfunction "2_2") (pintype "passive"))
      (node (ref "R76") (pin "2") (pinfunction "2_2") (pintype "passive"))
      (node (ref "R89") (pin "2") (pinfunction "2_2") (pintype "passive"))
      (node (ref "R92") (pin "2") (pinfunction "2_2") (pintype "passive"))
    )
    (net (code "6") (name "GND") (class "Default")
      (node (ref "C1") (pin "+") (pinfunction "+_+") (pintype "passive"))
      (node (ref "C11") (pin "2") (pinfunction "2_2") (pintype "passive"))
      (node (ref "C12") (pin "2") (pinfunction "2_2") (pintype "passive"))
      (node (ref "C13") (pin "2") (pinfunction "2_2") (pintype "passive"))
      (node (ref "C14") (pin "2") (pinfunction "2_2") (pintype "passive"))
      (node (ref "C15") (pin "2") (pinfunction "2_2") (pintype "passive"))
      (node (ref "C16") (pin "1") (pinfunction "1_1") (pintype "passive"))
      (node (ref "C17") (pin "1") (pinfunction "1_1") (pintype "passive"))
      (node (ref "C18") (pin "2") (pinfunction "2_2") (pintype "passive"))
      (node (ref "C2") (pin "-") (pinfunction "-_-") (pintype "passive"))
      (node (ref "C21") (pin "2") (pinfunction "2_2") (pintype "passive"))
      (node (ref "C22") (pin "1") (pinfunction "1_1") (pintype "passive"))
      (node (ref "C24") (pin "2") (pinfunction "2_2") (pintype "passive"))
      (node (ref "C25") (pin "2") (pinfunction "2_2") (pintype "passive"))
      (node (ref "C26") (pin "2") (pinfunction "2_2") (pintype "passive"))
      (node (ref "C27") (pin "2") (pinfunction "2_2") (pintype "passive"))
      (node (ref "C28") (pin "2") (pinfunction "2_2") (pintype "passive"))
      (node (ref "C29") (pin "1") (pinfunction "1_1") (pintype "passive"))
      (node (ref "C3") (pin "2") (pinfunction "2_2") (pintype "passive"))
      (node (ref "C30") (pin "2") (pinfunction "2_2") (pintype "passive"))
      (node (ref "C32") (pin "2") (pinfunction "2_2") (pintype "passive"))
      (node (ref "C33") (pin "1") (pinfunction "1_1") (pintype "passive"))
      (node (ref "C36") (pin "2") (pinfunction "2_2") (pintype "passive"))
      (node (ref "C37") (pin "2") (pinfunction "2_2") (pintype "passive"))
      (node (ref "C38") (pin "2") (pinfunction "2_2") (pintype "passive"))
      (node (ref "C39") (pin "2") (pinfunction "2_2") (pintype "passive"))
      (node (ref "C4") (pin "1") (pinfunction "1_1") (pintype "passive"))
      (node (ref "C40") (pin "2") (pinfunction "2_2") (pintype "passive"))
      (node (ref "C41") (pin "1") (pinfunction "1_1") (pintype "passive"))
      (node (ref "C42") (pin "1") (pinfunction "1_1") (pintype "passive"))
      (node (ref "C43") (pin "2") (pinfunction "2_2") (pintype "passive"))
      (node (ref "C46") (pin "2") (pinfunction "2_2") (pintype "passive"))
      (node (ref "C47") (pin "1") (pinfunction "1_1") (pintype "passive"))
      (node (ref "C5") (pin "2") (pinfunction "2_2") (pintype "passive"))
      (node (ref "C7") (pin "2") (pinfunction "2_2") (pintype "passive"))
      (node (ref "C8") (pin "1") (pinfunction "1_1") (pintype "passive"))
      (node (ref "D1") (pin "C") (pinfunction "C_C") (pintype "passive"))
      (node (ref "IC1") (pin "12") (pinfunction "+IN_12") (pintype "input"))
      (node (ref "IC1") (pin "3") (pinfunction "+IN_3") (pintype "input"))
      (node (ref "IC1") (pin "5") (pinfunction "+IN_5") (pintype "input"))
      (node (ref "IC10") (pin "8") (pinfunction "GND_8") (pintype "power_in"))
      (node (ref "IC11") (pin "12") (pinfunction "+IN_12") (pintype "input"))
      (node (ref "IC11") (pin "3") (pinfunction "+IN_3") (pintype "input"))
      (node (ref "IC11") (pin "5") (pinfunction "+IN_5") (pintype "input"))
      (node (ref "IC12") (pin "12") (pinfunction "+IN_12") (pintype "input"))
      (node (ref "IC12") (pin "3") (pinfunction "+IN_3") (pintype "input"))
      (node (ref "IC12") (pin "5") (pinfunction "+IN_5") (pintype "input"))
      (node (ref "IC2") (pin "12") (pinfunction "+IN_12") (pintype "input"))
      (node (ref "IC2") (pin "3") (pinfunction "+IN_3") (pintype "input"))
      (node (ref "IC2") (pin "5") (pinfunction "+IN_5") (pintype "input"))
      (node (ref "IC3") (pin "8") (pinfunction "GND_8") (pintype "power_in"))
      (node (ref "IC4") (pin "12") (pinfunction "+IN_12") (pintype "input"))
      (node (ref "IC4") (pin "3") (pinfunction "+IN_3") (pintype "input"))
      (node (ref "IC4") (pin "5") (pinfunction "+IN_5") (pintype "input"))
      (node (ref "IC5") (pin "12") (pinfunction "+IN_12") (pintype "input"))
      (node (ref "IC5") (pin "3") (pinfunction "+IN_3") (pintype "input"))
      (node (ref "IC5") (pin "5") (pinfunction "+IN_5") (pintype "input"))
      (node (ref "IC6") (pin "2") (pinfunction "A_2") (pintype "passive"))
      (node (ref "IC7") (pin "1") (pinfunction "C_1") (pintype "passive"))
      (node (ref "IC8") (pin "12") (pinfunction "+IN_12") (pintype "input"))
      (node (ref "IC8") (pin "3") (pinfunction "+IN_3") (pintype "input"))
      (node (ref "IC8") (pin "5") (pinfunction "+IN_5") (pintype "input"))
      (node (ref "IC9") (pin "12") (pinfunction "+IN_12") (pintype "input"))
      (node (ref "IC9") (pin "3") (pinfunction "+IN_3") (pintype "input"))
      (node (ref "IC9") (pin "5") (pinfunction "+IN_5") (pintype "input"))
      (node (ref "J1") (pin "P1") (pinfunction "1_P1") (pintype "passive"))
      (node (ref "J10") (pin "P1") (pinfunction "1_P1") (pintype "passive"))
      (node (ref "J11") (pin "P1") (pinfunction "1_P1") (pintype "passive"))
      (node (ref "J12") (pin "P1") (pinfunction "1_P1") (pintype "passive"))
      (node (ref "J12") (pin "P2") (pinfunction "2_P2") (pintype "passive"))
      (node (ref "J2") (pin "P1") (pinfunction "1_P1") (pintype "passive"))
      (node (ref "J3") (pin "P1") (pinfunction "1_P1") (pintype "passive"))
      (node (ref "J3") (pin "P2") (pinfunction "2_P2") (pintype "passive"))
      (node (ref "J4") (pin "P1") (pinfunction "1_P1") (pintype "passive"))
      (node (ref "J5") (pin "P1") (pinfunction "1_P1") (pintype "passive"))
      (node (ref "J6") (pin "P1") (pinfunction "1_P1") (pintype "passive"))
      (node (ref "J6") (pin "P2") (pinfunction "2_P2") (pintype "passive"))
      (node (ref "J7") (pin "P1") (pinfunction "1_P1") (pintype "passive"))
      (node (ref "J8") (pin "P1") (pinfunction "1_P1") (pintype "passive"))
      (node (ref "J9") (pin "P1") (pinfunction "1_P1") (pintype "passive"))
      (node (ref "J9") (pin "P2") (pinfunction "2_P2") (pintype "passive"))
      (node (ref "JP5") (pin "3") (pinfunction "3_3") (pintype "passive"))
      (node (ref "JP5") (pin "4") (pinfunction "4_4") (pintype "passive"))
      (node (ref "JP5") (pin "5") (pinfunction "5_5") (pintype "passive"))
      (node (ref "JP5") (pin "6") (pinfunction "6_6") (pintype "passive"))
      (node (ref "JP5") (pin "7") (pinfunction "7_7") (pintype "passive"))
      (node (ref "JP5") (pin "8") (pinfunction "8_8") (pintype "passive"))
      (node (ref "R108") (pin "2") (pinfunction "2_2") (pintype "passive"))
      (node (ref "R110") (pin "2") (pinfunction "2_2") (pintype "passive"))
      (node (ref "R113") (pin "2") (pinfunction "2_2") (pintype "passive"))
      (node (ref "R12") (pin "2") (pinfunction "2_2") (pintype "passive"))
      (node (ref "R15") (pin "2") (pinfunction "2_2") (pintype "passive"))
      (node (ref "R18") (pin "2") (pinfunction "2_2") (pintype "passive"))
      (node (ref "R21") (pin "2") (pinfunction "2_2") (pintype "passive"))
      (node (ref "R35") (pin "2") (pinfunction "2_2") (pintype "passive"))
      (node (ref "R36") (pin "P$3") (pinfunction "A_P$3") (pintype "passive"))
      (node (ref "R4") (pin "P$3") (pinfunction "A_P$3") (pintype "passive"))
      (node (ref "R48") (pin "2") (pinfunction "2_2") (pintype "passive"))
      (node (ref "R52") (pin "2") (pinfunction "2_2") (pintype "passive"))
      (node (ref "R53") (pin "2") (pinfunction "2_2") (pintype "passive"))
      (node (ref "R64") (pin "P$3") (pinfunction "A_P$3") (pintype "passive"))
      (node (ref "R72") (pin "2") (pinfunction "2_2") (pintype "passive"))
      (node (ref "R75") (pin "2") (pinfunction "2_2") (pintype "passive"))
      (node (ref "R77") (pin "2") (pinfunction "2_2") (pintype "passive"))
      (node (ref "R80") (pin "2") (pinfunction "2_2") (pintype "passive"))
      (node (ref "R96") (pin "2") (pinfunction "2_2") (pintype "passive"))
      (node (ref "R97") (pin "P$3") (pinfunction "A_P$3") (pintype "passive"))
    )
    (net (code "7") (name "Net-(C12-Pad1)") (class "Default")
      (node (ref "C12") (pin "1") (pinfunction "1_1") (pintype "passive"))
      (node (ref "R26") (pin "1") (pinfunction "1_1") (pintype "passive"))
    )
    (net (code "8") (name "Net-(C13-Pad1)") (class "Default")
      (node (ref "C13") (pin "1") (pinfunction "1_1") (pintype "passive"))
      (node (ref "R27") (pin "1") (pinfunction "1_1") (pintype "passive"))
    )
    (net (code "9") (name "Net-(C14-Pad1)") (class "Default")
      (node (ref "C14") (pin "1") (pinfunction "1_1") (pintype "passive"))
      (node (ref "R33") (pin "1") (pinfunction "1_1") (pintype "passive"))
    )
    (net (code "10") (name "Net-(C15-Pad1)") (class "Default")
      (node (ref "C15") (pin "1") (pinfunction "1_1") (pintype "passive"))
      (node (ref "R32") (pin "1") (pinfunction "1_1") (pintype "passive"))
    )
    (net (code "11") (name "Net-(C37-Pad1)") (class "Default")
      (node (ref "C37") (pin "1") (pinfunction "1_1") (pintype "passive"))
      (node (ref "R87") (pin "1") (pinfunction "1_1") (pintype "passive"))
    )
    (net (code "12") (name "Net-(C38-Pad1)") (class "Default")
      (node (ref "C38") (pin "1") (pinfunction "1_1") (pintype "passive"))
      (node (ref "R88") (pin "1") (pinfunction "1_1") (pintype "passive"))
    )
    (net (code "13") (name "Net-(C39-Pad1)") (class "Default")
      (node (ref "C39") (pin "1") (pinfunction "1_1") (pintype "passive"))
      (node (ref "R94") (pin "1") (pinfunction "1_1") (pintype "passive"))
    )
    (net (code "14") (name "Net-(C40-Pad1)") (class "Default")
      (node (ref "C40") (pin "1") (pinfunction "1_1") (pintype "passive"))
      (node (ref "R93") (pin "1") (pinfunction "1_1") (pintype "passive"))
    )
    (net (code "15") (name "Net-(D2-PadA)") (class "Default")
      (node (ref "D2") (pin "A") (pinfunction "A_A") (pintype "passive"))
      (node (ref "JP5") (pin "1") (pinfunction "1_1") (pintype "passive"))
      (node (ref "JP5") (pin "2") (pinfunction "2_2") (pintype "passive"))
    )
    (net (code "16") (name "Net-(D2-PadC)") (class "Default")
      (node (ref "D2") (pin "C") (pinfunction "C_C") (pintype "passive"))
      (node (ref "L1") (pin "2") (pinfunction "2_2") (pintype "passive"))
    )
    (net (code "17") (name "Net-(IC1A--IN)") (class "Default")
      (node (ref "IC1") (pin "2") (pinfunction "-IN_2") (pintype "input"))
      (node (ref "IC3") (pin "13") (pinfunction "OUT_13") (pintype "output"))
      (node (ref "R7") (pin "2") (pinfunction "2_2") (pintype "passive"))
    )
    (net (code "18") (name "Net-(IC1A-OUT)") (class "Default")
      (node (ref "IC1") (pin "1") (pinfunction "OUT_1") (pintype "output"))
      (node (ref "R13") (pin "2") (pinfunction "2_2") (pintype "passive"))
      (node (ref "R7") (pin "1") (pinfunction "1_1") (pintype "passive"))
    )
    (net (code "19") (name "Net-(IC1B--IN)") (class "Default")
      (node (ref "C9") (pin "1") (pinfunction "1_1") (pintype "passive"))
      (node (ref "IC1") (pin "6") (pinfunction "-IN_6") (pintype "input"))
      (node (ref "R13") (pin "1") (pinfunction "1_1") (pintype "passive"))
      (node (ref "R14") (pin "2") (pinfunction "2_2") (pintype "passive"))
      (node (ref "R23") (pin "1") (pinfunction "1_1") (pintype "passive"))
    )
    (net (code "20") (name "Net-(IC1B-OUT)") (class "Default")
      (node (ref "C9") (pin "2") (pinfunction "2_2") (pintype "passive"))
      (node (ref "IC1") (pin "7") (pinfunction "OUT_7") (pintype "output"))
      (node (ref "R14") (pin "1") (pinfunction "1_1") (pintype "passive"))
      (node (ref "R17") (pin "2") (pinfunction "2_2") (pintype "passive"))
      (node (ref "R24") (pin "2") (pinfunction "2_2") (pintype "passive"))
    )
    (net (code "21") (name "Net-(IC1C-+IN)") (class "Default")
      (node (ref "IC1") (pin "10") (pinfunction "+IN_10") (pintype "input"))
      (node (ref "R18") (pin "1") (pinfunction "1_1") (pintype "passive"))
      (node (ref "R24") (pin "1") (pinfunction "1_1") (pintype "passive"))
    )
    (net (code "22") (name "Net-(IC1C--IN)") (class "Default")
      (node (ref "IC1") (pin "9") (pinfunction "-IN_9") (pintype "input"))
      (node (ref "LED1") (pin "A") (pinfunction "A_A") (pintype "passive"))
      (node (ref "R15") (pin "1") (pinfunction "1_1") (pintype "passive"))
    )
    (net (code "23") (name "Net-(IC1C-OUT)") (class "Default")
      (node (ref "IC1") (pin "8") (pinfunction "OUT_8") (pintype "output"))
      (node (ref "LED1") (pin "K") (pinfunction "C_K") (pintype "passive"))
    )
    (net (code "24") (name "Net-(IC1D--IN)") (class "Default")
      (node (ref "IC1") (pin "13") (pinfunction "-IN_13") (pintype "input"))
      (node (ref "R10") (pin "1") (pinfunction "1_1") (pintype "passive"))
      (node (ref "R8") (pin "2") (pinfunction "2_2") (pintype "passive"))
    )
    (net (code "25") (name "Net-(IC2A--IN)") (class "Default")
      (node (ref "C6") (pin "2") (pinfunction "2_2") (pintype "passive"))
      (node (ref "IC2") (pin "2") (pinfunction "-IN_2") (pintype "input"))
      (node (ref "R1") (pin "1") (pinfunction "1_1") (pintype "passive"))
      (node (ref "R2") (pin "1") (pinfunction "1_1") (pintype "passive"))
      (node (ref "R4") (pin "P$1") (pinfunction "E_P$1") (pintype "passive"))
      (node (ref "R5") (pin "P$3") (pinfunction "A_P$3") (pintype "passive"))
      (node (ref "R6") (pin "2") (pinfunction "2_2") (pintype "passive"))
    )
    (net (code "26") (name "Net-(IC2A-OUT)") (class "Default")
      (node (ref "C6") (pin "1") (pinfunction "1_1") (pintype "passive"))
      (node (ref "IC2") (pin "1") (pinfunction "OUT_1") (pintype "output"))
      (node (ref "R22") (pin "2") (pinfunction "2_2") (pintype "passive"))
      (node (ref "R23") (pin "2") (pinfunction "2_2") (pintype "passive"))
      (node (ref "R29") (pin "2") (pinfunction "2_2") (pintype "passive"))
      (node (ref "R6") (pin "1") (pinfunction "1_1") (pintype "passive"))
    )
    (net (code "27") (name "Net-(IC2B--IN)") (class "Default")
      (node (ref "C10") (pin "1") (pinfunction "1_1") (pintype "passive"))
      (node (ref "IC2") (pin "6") (pinfunction "-IN_6") (pintype "input"))
      (node (ref "IC3") (pin "4") (pinfunction "OUT_4") (pintype "output"))
      (node (ref "R19") (pin "1") (pinfunction "1_1") (pintype "passive"))
      (node (ref "R20") (pin "1") (pinfunction "1_1") (pintype "passive"))
    )
    (net (code "28") (name "Net-(IC2B-OUT)") (class "Default")
      (node (ref "C10") (pin "2") (pinfunction "2_2") (pintype "passive"))
      (node (ref "IC2") (pin "7") (pinfunction "OUT_7") (pintype "output"))
      (node (ref "IC3") (pin "14") (pinfunction "CTRL_14") (pintype "input"))
      (node (ref "IC3") (pin "3") (pinfunction "CTRL_3") (pintype "input"))
    )
    (net (code "29") (name "Net-(IC2C-+IN)") (class "Default")
      (node (ref "IC2") (pin "10") (pinfunction "+IN_10") (pintype "input"))
      (node (ref "R12") (pin "1") (pinfunction "1_1") (pintype "passive"))
      (node (ref "R22") (pin "1") (pinfunction "1_1") (pintype "passive"))
    )
    (net (code "30") (name "Net-(IC2C--IN)") (class "Default")
      (node (ref "IC2") (pin "9") (pinfunction "-IN_9") (pintype "input"))
      (node (ref "LED2") (pin "A") (pinfunction "A_A") (pintype "passive"))
      (node (ref "R21") (pin "1") (pinfunction "1_1") (pintype "passive"))
    )
    (net (code "31") (name "Net-(IC2C-OUT)") (class "Default")
      (node (ref "IC2") (pin "8") (pinfunction "OUT_8") (pintype "output"))
      (node (ref "LED2") (pin "K") (pinfunction "C_K") (pintype "passive"))
    )
    (net (code "32") (name "Net-(IC2D--IN)") (class "Default")
      (node (ref "IC2") (pin "13") (pinfunction "-IN_13") (pintype "input"))
      (node (ref "R5") (pin "P$1") (pinfunction "E_P$1") (pintype "passive"))
      (node (ref "R9") (pin "2") (pinfunction "2_2") (pintype "passive"))
    )
    (net (code "33") (name "Net-(IC2D-OUT)") (class "Default")
      (node (ref "IC2") (pin "14") (pinfunction "OUT_14") (pintype "output"))
      (node (ref "R2") (pin "2") (pinfunction "2_2") (pintype "passive"))
      (node (ref "R9") (pin "1") (pinfunction "1_1") (pintype "passive"))
    )
    (net (code "34") (name "Net-(IC3A-IN)") (class "Default")
      (node (ref "IC3") (pin "2") (pinfunction "IN_2") (pintype "input"))
      (node (ref "R27") (pin "2") (pinfunction "2_2") (pintype "passive"))
      (node (ref "R28") (pin "1") (pinfunction "1_1") (pintype "passive"))
    )
    (net (code "35") (name "Net-(IC3B-CTRL)") (class "Default")
      (node (ref "C19") (pin "2") (pinfunction "2_2") (pintype "passive"))
      (node (ref "IC3") (pin "11") (pinfunction "CTRL_11") (pintype "input"))
      (node (ref "IC3") (pin "6") (pinfunction "CTRL_6") (pintype "input"))
      (node (ref "IC5") (pin "1") (pinfunction "OUT_1") (pintype "output"))
    )
    (net (code "36") (name "Net-(IC3B-IN)") (class "Default")
      (node (ref "IC3") (pin "7") (pinfunction "IN_7") (pintype "input"))
      (node (ref "R31") (pin "1") (pinfunction "1_1") (pintype "passive"))
      (node (ref "R33") (pin "2") (pinfunction "2_2") (pintype "passive"))
    )
    (net (code "37") (name "Net-(IC3B-OUT)") (class "Default")
      (node (ref "C19") (pin "1") (pinfunction "1_1") (pintype "passive"))
      (node (ref "IC3") (pin "5") (pinfunction "OUT_5") (pintype "output"))
      (node (ref "IC5") (pin "2") (pinfunction "-IN_2") (pintype "input"))
      (node (ref "R38") (pin "1") (pinfunction "1_1") (pintype "passive"))
      (node (ref "R39") (pin "1") (pinfunction "1_1") (pintype "passive"))
    )
    (net (code "38") (name "Net-(IC3C-IN)") (class "Default")
      (node (ref "IC3") (pin "10") (pinfunction "IN_10") (pintype "input"))
      (node (ref "R30") (pin "1") (pinfunction "1_1") (pintype "passive"))
      (node (ref "R32") (pin "2") (pinfunction "2_2") (pintype "passive"))
    )
    (net (code "39") (name "Net-(IC3C-OUT)") (class "Default")
      (node (ref "IC3") (pin "12") (pinfunction "OUT_12") (pintype "output"))
      (node (ref "IC4") (pin "2") (pinfunction "-IN_2") (pintype "input"))
      (node (ref "R40") (pin "2") (pinfunction "2_2") (pintype "passive"))
    )
    (net (code "40") (name "Net-(IC3D-IN)") (class "Default")
      (node (ref "IC3") (pin "15") (pinfunction "IN_15") (pintype "input"))
      (node (ref "R26") (pin "2") (pinfunction "2_2") (pintype "passive"))
      (node (ref "R29") (pin "1") (pinfunction "1_1") (pintype "passive"))
    )
    (net (code "41") (name "Net-(IC3E-MODE)") (class "Default")
      (node (ref "IC3") (pin "1") (pinfunction "MODE_1") (pintype "input"))
      (node (ref "R25") (pin "2") (pinfunction "2_2") (pintype "passive"))
    )
    (net (code "42") (name "Net-(IC4A-OUT)") (class "Default")
      (node (ref "IC4") (pin "1") (pinfunction "OUT_1") (pintype "output"))
      (node (ref "R40") (pin "1") (pinfunction "1_1") (pintype "passive"))
      (node (ref "R46") (pin "2") (pinfunction "2_2") (pintype "passive"))
    )
    (net (code "43") (name "Net-(IC4B--IN)") (class "Default")
      (node (ref "C20") (pin "1") (pinfunction "1_1") (pintype "passive"))
      (node (ref "IC4") (pin "6") (pinfunction "-IN_6") (pintype "input"))
      (node (ref "R46") (pin "1") (pinfunction "1_1") (pintype "passive"))
      (node (ref "R47") (pin "2") (pinfunction "2_2") (pintype "passive"))
      (node (ref "R54") (pin "1") (pinfunction "1_1") (pintype "passive"))
      (node (ref "R56") (pin "1") (pinfunction "1_1") (pintype "passive"))
    )
    (net (code "44") (name "Net-(IC4B-OUT)") (class "Default")
      (node (ref "C20") (pin "2") (pinfunction "2_2") (pintype "passive"))
      (node (ref "IC4") (pin "7") (pinfunction "OUT_7") (pintype "output"))
      (node (ref "R47") (pin "1") (pinfunction "1_1") (pintype "passive"))
      (node (ref "R55") (pin "2") (pinfunction "2_2") (pintype "passive"))
      (node (ref "R58") (pin "2") (pinfunction "2_2") (pintype "passive"))
    )
    (net (code "45") (name "Net-(IC4C-+IN)") (class "Default")
      (node (ref "IC4") (pin "10") (pinfunction "+IN_10") (pintype "input"))
      (node (ref "R52") (pin "1") (pinfunction "1_1") (pintype "passive"))
      (node (ref "R58") (pin "1") (pinfunction "1_1") (pintype "passive"))
    )
    (net (code "46") (name "Net-(IC4C--IN)") (class "Default")
      (node (ref "IC4") (pin "9") (pinfunction "-IN_9") (pintype "input"))
      (node (ref "LED3") (pin "A") (pinfunction "A_A") (pintype "passive"))
      (node (ref "R48") (pin "1") (pinfunction "1_1") (pintype "passive"))
    )
    (net (code "47") (name "Net-(IC4C-OUT)") (class "Default")
      (node (ref "IC4") (pin "8") (pinfunction "OUT_8") (pintype "output"))
      (node (ref "LED3") (pin "K") (pinfunction "C_K") (pintype "passive"))
    )
    (net (code "48") (name "Net-(IC4D--IN)") (class "Default")
      (node (ref "IC4") (pin "13") (pinfunction "-IN_13") (pintype "input"))
      (node (ref "R41") (pin "2") (pinfunction "2_2") (pintype "passive"))
      (node (ref "R44") (pin "1") (pinfunction "1_1") (pintype "passive"))
    )
    (net (code "49") (name "Net-(IC5B--IN)") (class "Default")
      (node (ref "C23") (pin "2") (pinfunction "2_2") (pintype "passive"))
      (node (ref "IC5") (pin "6") (pinfunction "-IN_6") (pintype "input"))
      (node (ref "R36") (pin "P$1") (pinfunction "E_P$1") (pintype "passive"))
      (node (ref "R37") (pin "P$3") (pinfunction "A_P$3") (pintype "passive"))
      (node (ref "R50") (pin "1") (pinfunction "1_1") (pintype "passive"))
      (node (ref "R51") (pin "2") (pinfunction "2_2") (pintype "passive"))
      (node (ref "R57") (pin "1") (pinfunction "1_1") (pintype "passive"))
    )
    (net (code "50") (name "Net-(IC5B-OUT)") (class "Default")
      (node (ref "C23") (pin "1") (pinfunction "1_1") (pintype "passive"))
      (node (ref "IC5") (pin "7") (pinfunction "OUT_7") (pintype "output"))
      (node (ref "R30") (pin "2") (pinfunction "2_2") (pintype "passive"))
      (node (ref "R42") (pin "2") (pinfunction "2_2") (pintype "passive"))
      (node (ref "R51") (pin "1") (pinfunction "1_1") (pintype "passive"))
      (node (ref "R54") (pin "2") (pinfunction "2_2") (pintype "passive"))
    )
    (net (code "51") (name "Net-(IC5C-+IN)") (class "Default")
      (node (ref "IC5") (pin "10") (pinfunction "+IN_10") (pintype "input"))
      (node (ref "R35") (pin "1") (pinfunction "1_1") (pintype "passive"))
      (node (ref "R42") (pin "1") (pinfunction "1_1") (pintype "passive"))
    )
    (net (code "52") (name "Net-(IC5C--IN)") (class "Default")
      (node (ref "IC5") (pin "9") (pinfunction "-IN_9") (pintype "input"))
      (node (ref "LED4") (pin "A") (pinfunction "A_A") (pintype "passive"))
      (node (ref "R53") (pin "1") (pinfunction "1_1") (pintype "passive"))
    )
    (net (code "53") (name "Net-(IC5C-OUT)") (class "Default")
      (node (ref "IC5") (pin "8") (pinfunction "OUT_8") (pintype "output"))
      (node (ref "LED4") (pin "K") (pinfunction "C_K") (pintype "passive"))
    )
    (net (code "54") (name "Net-(IC5D--IN)") (class "Default")
      (node (ref "IC5") (pin "13") (pinfunction "-IN_13") (pintype "input"))
      (node (ref "R37") (pin "P$1") (pinfunction "E_P$1") (pintype "passive"))
      (node (ref "R43") (pin "2") (pinfunction "2_2") (pintype "passive"))
    )
    (net (code "55") (name "Net-(IC5D-OUT)") (class "Default")
      (node (ref "IC5") (pin "14") (pinfunction "OUT_14") (pintype "output"))
      (node (ref "R43") (pin "1") (pinfunction "1_1") (pintype "passive"))
      (node (ref "R50") (pin "2") (pinfunction "2_2") (pintype "passive"))
    )
    (net (code "56") (name "Net-(IC8A-OUT)") (class "Default")
      (node (ref "IC8") (pin "1") (pinfunction "OUT_1") (pintype "output"))
      (node (ref "R67") (pin "1") (pinfunction "1_1") (pintype "passive"))
      (node (ref "R73") (pin "2") (pinfunction "2_2") (pintype "passive"))
    )
    (net (code "57") (name "Net-(IC8B--IN)") (class "Default")
      (node (ref "C34") (pin "1") (pinfunction "1_1") (pintype "passive"))
      (node (ref "IC8") (pin "6") (pinfunction "-IN_6") (pintype "input"))
      (node (ref "R73") (pin "1") (pinfunction "1_1") (pintype "passive"))
      (node (ref "R74") (pin "2") (pinfunction "2_2") (pintype "passive"))
      (node (ref "R82") (pin "1") (pinfunction "1_1") (pintype "passive"))
      (node (ref "R83") (pin "1") (pinfunction "1_1") (pintype "passive"))
    )
    (net (code "58") (name "Net-(IC8B-OUT)") (class "Default")
      (node (ref "C34") (pin "2") (pinfunction "2_2") (pintype "passive"))
      (node (ref "IC8") (pin "7") (pinfunction "OUT_7") (pintype "output"))
      (node (ref "R74") (pin "1") (pinfunction "1_1") (pintype "passive"))
      (node (ref "R84") (pin "2") (pinfunction "2_2") (pintype "passive"))
      (node (ref "R85") (pin "2") (pinfunction "2_2") (pintype "passive"))
    )
    (net (code "59") (name "Net-(IC8C-+IN)") (class "Default")
      (node (ref "IC8") (pin "10") (pinfunction "+IN_10") (pintype "input"))
      (node (ref "R77") (pin "1") (pinfunction "1_1") (pintype "passive"))
      (node (ref "R85") (pin "1") (pinfunction "1_1") (pintype "passive"))
    )
    (net (code "60") (name "Net-(IC8C--IN)") (class "Default")
      (node (ref "IC8") (pin "9") (pinfunction "-IN_9") (pintype "input"))
      (node (ref "LED5") (pin "A") (pinfunction "A_A") (pintype "passive"))
      (node (ref "R75") (pin "1") (pinfunction "1_1") (pintype "passive"))
    )
    (net (code "61") (name "Net-(IC8C-OUT)") (class "Default")
      (node (ref "IC8") (pin "8") (pinfunction "OUT_8") (pintype "output"))
      (node (ref "LED5") (pin "K") (pinfunction "C_K") (pintype "passive"))
    )
    (net (code "62") (name "Net-(IC8D--IN)") (class "Default")
      (node (ref "IC8") (pin "13") (pinfunction "-IN_13") (pintype "input"))
      (node (ref "R68") (pin "2") (pinfunction "2_2") (pintype "passive"))
      (node (ref "R70") (pin "1") (pinfunction "1_1") (pintype "passive"))
    )
    (net (code "63") (name "Net-(IC9A--IN)") (class "Default")
      (node (ref "C31") (pin "2") (pinfunction "2_2") (pintype "passive"))
      (node (ref "IC9") (pin "2") (pinfunction "-IN_2") (pintype "input"))
      (node (ref "R61") (pin "1") (pinfunction "1_1") (pintype "passive"))
      (node (ref "R62") (pin "1") (pinfunction "1_1") (pintype "passive"))
      (node (ref "R64") (pin "P$1") (pinfunction "E_P$1") (pintype "passive"))
      (node (ref "R65") (pin "P$3") (pinfunction "A_P$3") (pintype "passive"))
      (node (ref "R66") (pin "2") (pinfunction "2_2") (pintype "passive"))
    )
    (net (code "64") (name "Net-(IC9A-OUT)") (class "Default")
      (node (ref "C31") (pin "1") (pinfunction "1_1") (pintype "passive"))
      (node (ref "IC9") (pin "1") (pinfunction "OUT_1") (pintype "output"))
      (node (ref "R66") (pin "1") (pinfunction "1_1") (pintype "passive"))
      (node (ref "R81") (pin "2") (pinfunction "2_2") (pintype "passive"))
      (node (ref "R83") (pin "2") (pinfunction "2_2") (pintype "passive"))
      (node (ref "R90") (pin "2") (pinfunction "2_2") (pintype "passive"))
    )
    (net (code "65") (name "Net-(IC9C-+IN)") (class "Default")
      (node (ref "IC9") (pin "10") (pinfunction "+IN_10") (pintype "input"))
      (node (ref "R72") (pin "1") (pinfunction "1_1") (pintype "passive"))
      (node (ref "R81") (pin "1") (pinfunction "1_1") (pintype "passive"))
    )
    (net (code "66") (name "Net-(IC9C--IN)") (class "Default")
      (node (ref "IC9") (pin "9") (pinfunction "-IN_9") (pintype "input"))
      (node (ref "LED6") (pin "A") (pinfunction "A_A") (pintype "passive"))
      (node (ref "R80") (pin "1") (pinfunction "1_1") (pintype "passive"))
    )
    (net (code "67") (name "Net-(IC9C-OUT)") (class "Default")
      (node (ref "IC9") (pin "8") (pinfunction "OUT_8") (pintype "output"))
      (node (ref "LED6") (pin "K") (pinfunction "C_K") (pintype "passive"))
    )
    (net (code "68") (name "Net-(IC9D--IN)") (class "Default")
      (node (ref "IC9") (pin "13") (pinfunction "-IN_13") (pintype "input"))
      (node (ref "R65") (pin "P$1") (pinfunction "E_P$1") (pintype "passive"))
      (node (ref "R69") (pin "2") (pinfunction "2_2") (pintype "passive"))
    )
    (net (code "69") (name "Net-(IC9D-OUT)") (class "Default")
      (node (ref "IC9") (pin "14") (pinfunction "OUT_14") (pintype "output"))
      (node (ref "R62") (pin "2") (pinfunction "2_2") (pintype "passive"))
      (node (ref "R69") (pin "1") (pinfunction "1_1") (pintype "passive"))
    )
    (net (code "70") (name "Net-(IC10A-CTRL)") (class "Default")
      (node (ref "C35") (pin "2") (pinfunction "2_2") (pintype "passive"))
      (node (ref "IC10") (pin "14") (pinfunction "CTRL_14") (pintype "input"))
      (node (ref "IC10") (pin "3") (pinfunction "CTRL_3") (pintype "input"))
      (node (ref "IC9") (pin "7") (pinfunction "OUT_7") (pintype "output"))
    )
    (net (code "71") (name "Net-(IC10A-IN)") (class "Default")
      (node (ref "IC10") (pin "2") (pinfunction "IN_2") (pintype "input"))
      (node (ref "R88") (pin "2") (pinfunction "2_2") (pintype "passive"))
      (node (ref "R89") (pin "1") (pinfunction "1_1") (pintype "passive"))
    )
    (net (code "72") (name "Net-(IC10A-OUT)") (class "Default")
      (node (ref "C35") (pin "1") (pinfunction "1_1") (pintype "passive"))
      (node (ref "IC10") (pin "4") (pinfunction "OUT_4") (pintype "output"))
      (node (ref "IC9") (pin "6") (pinfunction "-IN_6") (pintype "input"))
      (node (ref "R78") (pin "1") (pinfunction "1_1") (pintype "passive"))
      (node (ref "R79") (pin "1") (pinfunction "1_1") (pintype "passive"))
    )
    (net (code "73") (name "Net-(IC10B-CTRL)") (class "Default")
      (node (ref "C44") (pin "2") (pinfunction "2_2") (pintype "passive"))
      (node (ref "IC10") (pin "11") (pinfunction "CTRL_11") (pintype "input"))
      (node (ref "IC10") (pin "6") (pinfunction "CTRL_6") (pintype "input"))
      (node (ref "IC12") (pin "1") (pinfunction "OUT_1") (pintype "output"))
    )
    (net (code "74") (name "Net-(IC10B-IN)") (class "Default")
      (node (ref "IC10") (pin "7") (pinfunction "IN_7") (pintype "input"))
      (node (ref "R92") (pin "1") (pinfunction "1_1") (pintype "passive"))
      (node (ref "R94") (pin "2") (pinfunction "2_2") (pintype "passive"))
    )
    (net (code "75") (name "Net-(IC10B-OUT)") (class "Default")
      (node (ref "C44") (pin "1") (pinfunction "1_1") (pintype "passive"))
      (node (ref "IC10") (pin "5") (pinfunction "OUT_5") (pintype "output"))
      (node (ref "IC12") (pin "2") (pinfunction "-IN_2") (pintype "input"))
      (node (ref "R101") (pin "1") (pinfunction "1_1") (pintype "passive"))
      (node (ref "R102") (pin "1") (pinfunction "1_1") (pintype "passive"))
    )
    (net (code "76") (name "Net-(IC10C-IN)") (class "Default")
      (node (ref "IC10") (pin "10") (pinfunction "IN_10") (pintype "input"))
      (node (ref "R91") (pin "1") (pinfunction "1_1") (pintype "passive"))
      (node (ref "R93") (pin "2") (pinfunction "2_2") (pintype "passive"))
    )
    (net (code "77") (name "Net-(IC10C-OUT)") (class "Default")
      (node (ref "IC10") (pin "12") (pinfunction "OUT_12") (pintype "output"))
      (node (ref "IC11") (pin "2") (pinfunction "-IN_2") (pintype "input"))
      (node (ref "R100") (pin "2") (pinfunction "2_2") (pintype "passive"))
    )
    (net (code "78") (name "Net-(IC10D-IN)") (class "Default")
      (node (ref "IC10") (pin "15") (pinfunction "IN_15") (pintype "input"))
      (node (ref "R87") (pin "2") (pinfunction "2_2") (pintype "passive"))
      (node (ref "R90") (pin "1") (pinfunction "1_1") (pintype "passive"))
    )
    (net (code "79") (name "Net-(IC10D-OUT)") (class "Default")
      (node (ref "IC10") (pin "13") (pinfunction "OUT_13") (pintype "output"))
      (node (ref "IC8") (pin "2") (pinfunction "-IN_2") (pintype "input"))
      (node (ref "R67") (pin "2") (pinfunction "2_2") (pintype "passive"))
    )
    (net (code "80") (name "Net-(IC10E-MODE)") (class "Default")
      (node (ref "IC10") (pin "1") (pinfunction "MODE_1") (pintype "input"))
      (node (ref "R86") (pin "2") (pinfunction "2_2") (pintype "passive"))
    )
    (net (code "81") (name "Net-(IC11A-OUT)") (class "Default")
      (node (ref "IC11") (pin "1") (pinfunction "OUT_1") (pintype "output"))
      (node (ref "R100") (pin "1") (pinfunction "1_1") (pintype "passive"))
      (node (ref "R99") (pin "2") (pinfunction "2_2") (pintype "passive"))
    )
    (net (code "82") (name "Net-(IC11B--IN)") (class "Default")
      (node (ref "C45") (pin "1") (pinfunction "1_1") (pintype "passive"))
      (node (ref "IC11") (pin "6") (pinfunction "-IN_6") (pintype "input"))
      (node (ref "R103") (pin "1") (pinfunction "1_1") (pintype "passive"))
      (node (ref "R107") (pin "2") (pinfunction "2_2") (pintype "passive"))
      (node (ref "R114") (pin "1") (pinfunction "1_1") (pintype "passive"))
      (node (ref "R99") (pin "1") (pinfunction "1_1") (pintype "passive"))
    )
    (net (code "83") (name "Net-(IC11B-OUT)") (class "Default")
      (node (ref "C45") (pin "2") (pinfunction "2_2") (pintype "passive"))
      (node (ref "IC11") (pin "7") (pinfunction "OUT_7") (pintype "output"))
      (node (ref "R107") (pin "1") (pinfunction "1_1") (pintype "passive"))
      (node (ref "R115") (pin "2") (pinfunction "2_2") (pintype "passive"))
      (node (ref "R116") (pin "2") (pinfunction "2_2") (pintype "passive"))
    )
    (net (code "84") (name "Net-(IC11C-+IN)") (class "Default")
      (node (ref "IC11") (pin "10") (pinfunction "+IN_10") (pintype "input"))
      (node (ref "R110") (pin "1") (pinfunction "1_1") (pintype "passive"))
      (node (ref "R115") (pin "1") (pinfunction "1_1") (pintype "passive"))
    )
    (net (code "85") (name "Net-(IC11C--IN)") (class "Default")
      (node (ref "IC11") (pin "9") (pinfunction "-IN_9") (pintype "input"))
      (node (ref "LED7") (pin "A") (pinfunction "A_A") (pintype "passive"))
      (node (ref "R108") (pin "1") (pinfunction "1_1") (pintype "passive"))
    )
    (net (code "86") (name "Net-(IC11C-OUT)") (class "Default")
      (node (ref "IC11") (pin "8") (pinfunction "OUT_8") (pintype "output"))
      (node (ref "LED7") (pin "K") (pinfunction "C_K") (pintype "passive"))
    )
    (net (code "87") (name "Net-(IC11D--IN)") (class "Default")
      (node (ref "IC11") (pin "13") (pinfunction "-IN_13") (pintype "input"))
      (node (ref "IC11") (pin "14") (pinfunction "OUT_14") (pintype "output"))
    )
    (net (code "88") (name "Net-(IC12B--IN)") (class "Default")
      (node (ref "C48") (pin "2") (pinfunction "2_2") (pintype "passive"))
      (node (ref "IC12") (pin "6") (pinfunction "-IN_6") (pintype "input"))
      (node (ref "R111") (pin "1") (pinfunction "1_1") (pintype "passive"))
      (node (ref "R112") (pin "2") (pinfunction "2_2") (pintype "passive"))
      (node (ref "R117") (pin "1") (pinfunction "1_1") (pintype "passive"))
      (node (ref "R97") (pin "P$1") (pinfunction "E_P$1") (pintype "passive"))
      (node (ref "R98") (pin "P$3") (pinfunction "A_P$3") (pintype "passive"))
    )
    (net (code "89") (name "Net-(IC12B-OUT)") (class "Default")
      (node (ref "C48") (pin "1") (pinfunction "1_1") (pintype "passive"))
      (node (ref "IC12") (pin "7") (pinfunction "OUT_7") (pintype "output"))
      (node (ref "R103") (pin "2") (pinfunction "2_2") (pintype "passive"))
      (node (ref "R104") (pin "2") (pinfunction "2_2") (pintype "passive"))
      (node (ref "R112") (pin "1") (pinfunction "1_1") (pintype "passive"))
      (node (ref "R91") (pin "2") (pinfunction "2_2") (pintype "passive"))
    )
    (net (code "90") (name "Net-(IC12C-+IN)") (class "Default")
      (node (ref "IC12") (pin "10") (pinfunction "+IN_10") (pintype "input"))
      (node (ref "R104") (pin "1") (pinfunction "1_1") (pintype "passive"))
      (node (ref "R96") (pin "1") (pinfunction "1_1") (pintype "passive"))
    )
    (net (code "91") (name "Net-(IC12C--IN)") (class "Default")
      (node (ref "IC12") (pin "9") (pinfunction "-IN_9") (pintype "input"))
      (node (ref "LED8") (pin "A") (pinfunction "A_A") (pintype "passive"))
      (node (ref "R113") (pin "1") (pinfunction "1_1") (pintype "passive"))
    )
    (net (code "92") (name "Net-(IC12C-OUT)") (class "Default")
      (node (ref "IC12") (pin "8") (pinfunction "OUT_8") (pintype "output"))
      (node (ref "LED8") (pin "K") (pinfunction "C_K") (pintype "passive"))
    )
    (net (code "93") (name "Net-(IC12D--IN)") (class "Default")
      (node (ref "IC12") (pin "13") (pinfunction "-IN_13") (pintype "input"))
      (node (ref "R105") (pin "2") (pinfunction "2_2") (pintype "passive"))
      (node (ref "R98") (pin "P$1") (pinfunction "E_P$1") (pintype "passive"))
    )
    (net (code "94") (name "Net-(IC12D-OUT)") (class "Default")
      (node (ref "IC12") (pin "14") (pinfunction "OUT_14") (pintype "output"))
      (node (ref "R105") (pin "1") (pinfunction "1_1") (pintype "passive"))
      (node (ref "R111") (pin "2") (pinfunction "2_2") (pintype "passive"))
    )
    (net (code "95") (name "Net-(J1-2)") (class "Default")
      (node (ref "J1") (pin "P2") (pinfunction "2_P2") (pintype "passive"))
      (node (ref "R3") (pin "2") (pinfunction "2_2") (pintype "passive"))
    )
    (net (code "96") (name "Net-(J1-3)") (class "Default")
      (node (ref "J1") (pin "P3") (pinfunction "3_P3") (pintype "passive"))
      (node (ref "R19") (pin "2") (pinfunction "2_2") (pintype "passive"))
    )
    (net (code "97") (name "Net-(J2-2)") (class "Default")
      (node (ref "J2") (pin "P2") (pinfunction "2_P2") (pintype "passive"))
      (node (ref "R10") (pin "2") (pinfunction "2_2") (pintype "passive"))
    )
    (net (code "98") (name "Net-(J2-3)") (class "Default")
      (node (ref "J2") (pin "P3") (pinfunction "3_P3") (pintype "passive"))
      (node (ref "R17") (pin "1") (pinfunction "1_1") (pintype "passive"))
    )
    (net (code "99") (name "Net-(J3-3)") (class "Default")
      (node (ref "J3") (pin "P3") (pinfunction "3_P3") (pintype "passive"))
      (node (ref "R11") (pin "2") (pinfunction "2_2") (pintype "passive"))
    )
    (net (code "100") (name "Net-(J4-2)") (class "Default")
      (node (ref "J4") (pin "P2") (pinfunction "2_P2") (pintype "passive"))
      (node (ref "R34") (pin "2") (pinfunction "2_2") (pintype "passive"))
    )
    (net (code "101") (name "Net-(J4-3)") (class "Default")
      (node (ref "J4") (pin "P3") (pinfunction "3_P3") (pintype "passive"))
      (node (ref "R39") (pin "2") (pinfunction "2_2") (pintype "passive"))
    )
    (net (code "102") (name "Net-(J5-2)") (class "Default")
      (node (ref "J5") (pin "P2") (pinfunction "2_P2") (pintype "passive"))
      (node (ref "R44") (pin "2") (pinfunction "2_2") (pintype "passive"))
    )
    (net (code "103") (name "Net-(J5-3)") (class "Default")
      (node (ref "J5") (pin "P3") (pinfunction "3_P3") (pintype "passive"))
      (node (ref "R55") (pin "1") (pinfunction "1_1") (pintype "passive"))
    )
    (net (code "104") (name "Net-(J6-3)") (class "Default")
      (node (ref "J6") (pin "P3") (pinfunction "3_P3") (pintype "passive"))
      (node (ref "R45") (pin "2") (pinfunction "2_2") (pintype "passive"))
    )
    (net (code "105") (name "Net-(J7-2)") (class "Default")
      (node (ref "J7") (pin "P2") (pinfunction "2_P2") (pintype "passive"))
      (node (ref "R63") (pin "2") (pinfunction "2_2") (pintype "passive"))
    )
    (net (code "106") (name "Net-(J7-3)") (class "Default")
      (node (ref "J7") (pin "P3") (pinfunction "3_P3") (pintype "passive"))
      (node (ref "R78") (pin "2") (pinfunction "2_2") (pintype "passive"))
    )
    (net (code "107") (name "Net-(J8-2)") (class "Default")
      (node (ref "J8") (pin "P2") (pinfunction "2_P2") (pintype "passive"))
      (node (ref "R70") (pin "2") (pinfunction "2_2") (pintype "passive"))
    )
    (net (code "108") (name "Net-(J8-3)") (class "Default")
      (node (ref "J8") (pin "P3") (pinfunction "3_P3") (pintype "passive"))
      (node (ref "R84") (pin "1") (pinfunction "1_1") (pintype "passive"))
    )
    (net (code "109") (name "Net-(J9-3)") (class "Default")
      (node (ref "J9") (pin "P3") (pinfunction "3_P3") (pintype "passive"))
      (node (ref "R71") (pin "2") (pinfunction "2_2") (pintype "passive"))
    )
    (net (code "110") (name "Net-(J10-2)") (class "Default")
      (node (ref "J10") (pin "P2") (pinfunction "2_P2") (pintype "passive"))
      (node (ref "R95") (pin "2") (pinfunction "2_2") (pintype "passive"))
    )
    (net (code "111") (name "Net-(J10-3)") (class "Default")
      (node (ref "J10") (pin "P3") (pinfunction "3_P3") (pintype "passive"))
      (node (ref "R102") (pin "2") (pinfunction "2_2") (pintype "passive"))
    )
    (net (code "112") (name "Net-(J11-3)") (class "Default")
      (node (ref "J11") (pin "P3") (pinfunction "3_P3") (pintype "passive"))
      (node (ref "R116") (pin "1") (pinfunction "1_1") (pintype "passive"))
    )
    (net (code "113") (name "Net-(J12-3)") (class "Default")
      (node (ref "J12") (pin "P3") (pinfunction "3_P3") (pintype "passive"))
      (node (ref "R106") (pin "2") (pinfunction "2_2") (pintype "passive"))
    )
    (net (code "114") (name "Net-(JP5-Pad10)") (class "Default")
      (node (ref "JP5") (pin "10") (pinfunction "10_10") (pintype "passive"))
      (node (ref "JP5") (pin "9") (pinfunction "9_9") (pintype "passive"))
      (node (ref "P1") (pin "2") (pinfunction "2_2") (pintype "bidirectional"))
    )
    (net (code "115") (name "Net-(L2-Pad2)") (class "Default")
      (node (ref "L2") (pin "2") (pinfunction "2_2") (pintype "passive"))
      (node (ref "P1") (pin "1") (pinfunction "1_1") (pintype "bidirectional"))
    )
    (net (code "116") (name "Net-(R4-S)") (class "Default")
      (node (ref "R16") (pin "1") (pinfunction "1_1") (pintype "passive"))
      (node (ref "R4") (pin "P$2") (pinfunction "S_P$2") (pintype "passive"))
    )
    (net (code "117") (name "Net-(R5-S)") (class "Default")
      (node (ref "R11") (pin "1") (pinfunction "1_1") (pintype "passive"))
      (node (ref "R5") (pin "P$2") (pinfunction "S_P$2") (pintype "passive"))
    )
    (net (code "118") (name "Net-(R36-S)") (class "Default")
      (node (ref "R36") (pin "P$2") (pinfunction "S_P$2") (pintype "passive"))
      (node (ref "R49") (pin "1") (pinfunction "1_1") (pintype "passive"))
    )
    (net (code "119") (name "Net-(R37-S)") (class "Default")
      (node (ref "R37") (pin "P$2") (pinfunction "S_P$2") (pintype "passive"))
      (node (ref "R45") (pin "1") (pinfunction "1_1") (pintype "passive"))
    )
    (net (code "120") (name "Net-(R64-S)") (class "Default")
      (node (ref "R64") (pin "P$2") (pinfunction "S_P$2") (pintype "passive"))
      (node (ref "R76") (pin "1") (pinfunction "1_1") (pintype "passive"))
    )
    (net (code "121") (name "Net-(R65-S)") (class "Default")
      (node (ref "R65") (pin "P$2") (pinfunction "S_P$2") (pintype "passive"))
      (node (ref "R71") (pin "1") (pinfunction "1_1") (pintype "passive"))
    )
    (net (code "122") (name "Net-(R97-S)") (class "Default")
      (node (ref "R109") (pin "1") (pinfunction "1_1") (pintype "passive"))
      (node (ref "R97") (pin "P$2") (pinfunction "S_P$2") (pintype "passive"))
    )
    (net (code "123") (name "Net-(R98-S)") (class "Default")
      (node (ref "R106") (pin "1") (pinfunction "1_1") (pintype "passive"))
      (node (ref "R98") (pin "P$2") (pinfunction "S_P$2") (pintype "passive"))
    )
    (net (code "124") (name "VCC") (class "Default")
      (node (ref "C11") (pin "1") (pinfunction "1_1") (pintype "passive"))
      (node (ref "C18") (pin "1") (pinfunction "1_1") (pintype "passive"))
      (node (ref "C2") (pin "+") (pinfunction "+_+") (pintype "passive"))
      (node (ref "C21") (pin "1") (pinfunction "1_1") (pintype "passive"))
      (node (ref "C24") (pin "1") (pinfunction "1_1") (pintype "passive"))
      (node (ref "C30") (pin "1") (pinfunction "1_1") (pintype "passive"))
      (node (ref "C32") (pin "1") (pinfunction "1_1") (pintype "passive"))
      (node (ref "C36") (pin "1") (pinfunction "1_1") (pintype "passive"))
      (node (ref "C43") (pin "1") (pinfunction "1_1") (pintype "passive"))
      (node (ref "C46") (pin "1") (pinfunction "1_1") (pintype "passive"))
      (node (ref "C5") (pin "1") (pinfunction "1_1") (pintype "passive"))
      (node (ref "C7") (pin "1") (pinfunction "1_1") (pintype "passive"))
      (node (ref "IC1") (pin "4") (pinfunction "V+_4") (pintype "power_in"))
      (node (ref "IC10") (pin "16") (pinfunction "V+_16") (pintype "power_in"))
      (node (ref "IC11") (pin "4") (pinfunction "V+_4") (pintype "power_in"))
      (node (ref "IC12") (pin "4") (pinfunction "V+_4") (pintype "power_in"))
      (node (ref "IC2") (pin "4") (pinfunction "V+_4") (pintype "power_in"))
      (node (ref "IC3") (pin "16") (pinfunction "V+_16") (pintype "power_in"))
      (node (ref "IC4") (pin "4") (pinfunction "V+_4") (pintype "power_in"))
      (node (ref "IC5") (pin "4") (pinfunction "V+_4") (pintype "power_in"))
      (node (ref "IC8") (pin "4") (pinfunction "V+_4") (pintype "power_in"))
      (node (ref "IC9") (pin "4") (pinfunction "V+_4") (pintype "power_in"))
      (node (ref "L1") (pin "1") (pinfunction "1_1") (pintype "passive"))
      (node (ref "R25") (pin "1") (pinfunction "1_1") (pintype "passive"))
      (node (ref "R59") (pin "1") (pinfunction "1_1") (pintype "passive"))
      (node (ref "R86") (pin "1") (pinfunction "1_1") (pintype "passive"))
    )
    (net (code "125") (name "VEE") (class "Default")
      (node (ref "C1") (pin "-") (pinfunction "-_-") (pintype "passive"))
      (node (ref "C16") (pin "2") (pinfunction "2_2") (pintype "passive"))
      (node (ref "C17") (pin "2") (pinfunction "2_2") (pintype "passive"))
      (node (ref "C22") (pin "2") (pinfunction "2_2") (pintype "passive"))
      (node (ref "C25") (pin "1") (pinfunction "1_1") (pintype "passive"))
      (node (ref "C29") (pin "2") (pinfunction "2_2") (pintype "passive"))
      (node (ref "C33") (pin "2") (pinfunction "2_2") (pintype "passive"))
      (node (ref "C4") (pin "2") (pinfunction "2_2") (pintype "passive"))
      (node (ref "C41") (pin "2") (pinfunction "2_2") (pintype "passive"))
      (node (ref "C42") (pin "2") (pinfunction "2_2") (pintype "passive"))
      (node (ref "C47") (pin "2") (pinfunction "2_2") (pintype "passive"))
      (node (ref "C8") (pin "2") (pinfunction "2_2") (pintype "passive"))
      (node (ref "D1") (pin "A") (pinfunction "A_A") (pintype "passive"))
      (node (ref "IC1") (pin "11") (pinfunction "V-_11") (pintype "power_in"))
      (node (ref "IC10") (pin "9") (pinfunction "V-_9") (pintype "power_in"))
      (node (ref "IC11") (pin "11") (pinfunction "V-_11") (pintype "power_in"))
      (node (ref "IC12") (pin "11") (pinfunction "V-_11") (pintype "power_in"))
      (node (ref "IC2") (pin "11") (pinfunction "V-_11") (pintype "power_in"))
      (node (ref "IC3") (pin "9") (pinfunction "V-_9") (pintype "power_in"))
      (node (ref "IC4") (pin "11") (pinfunction "V-_11") (pintype "power_in"))
      (node (ref "IC5") (pin "11") (pinfunction "V-_11") (pintype "power_in"))
      (node (ref "IC8") (pin "11") (pinfunction "V-_11") (pintype "power_in"))
      (node (ref "IC9") (pin "11") (pinfunction "V-_11") (pintype "power_in"))
      (node (ref "L2") (pin "1") (pinfunction "1_1") (pintype "passive"))
      (node (ref "R60") (pin "1") (pinfunction "1_1") (pintype "passive"))
    )
    (net (code "126") (name "unconnected-(J11-2-PadP2)") (class "Default")
      (node (ref "J11") (pin "P2") (pinfunction "2_P2") (pintype "passive"))
    )
  )
)
